# DRV10987.net
KiCad netlist of a schematic drawn in EAGLE
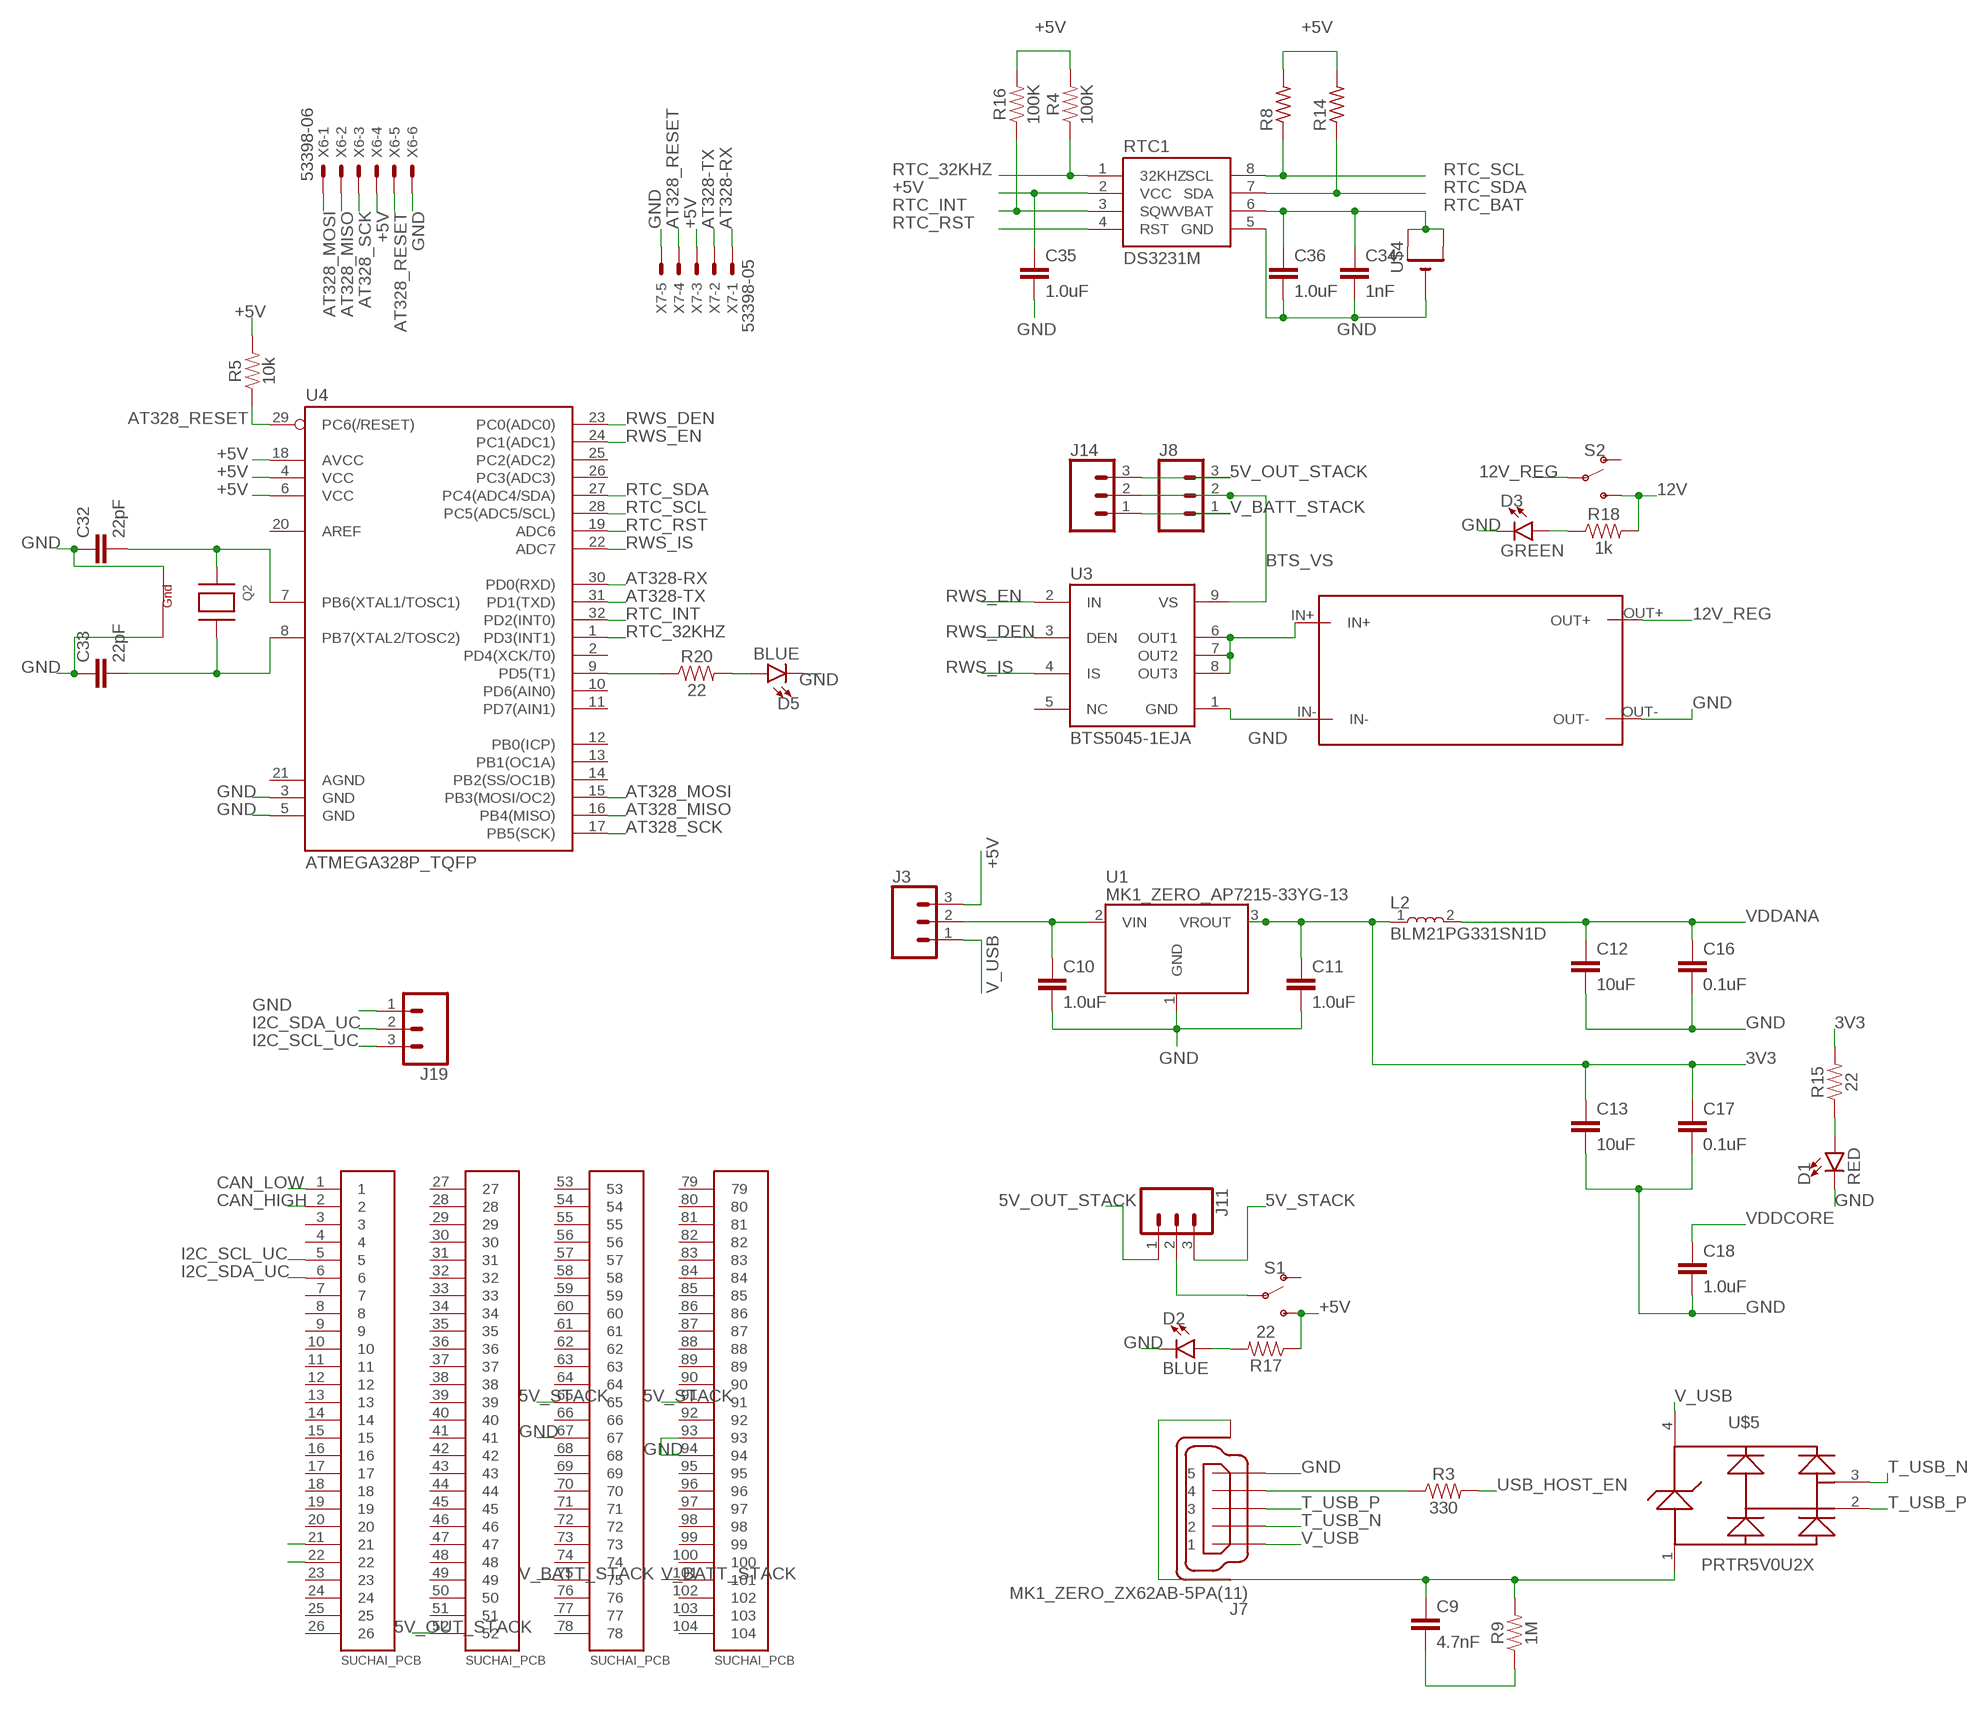
[diagram p0: schematic, sheet 1, part 1 of 2]
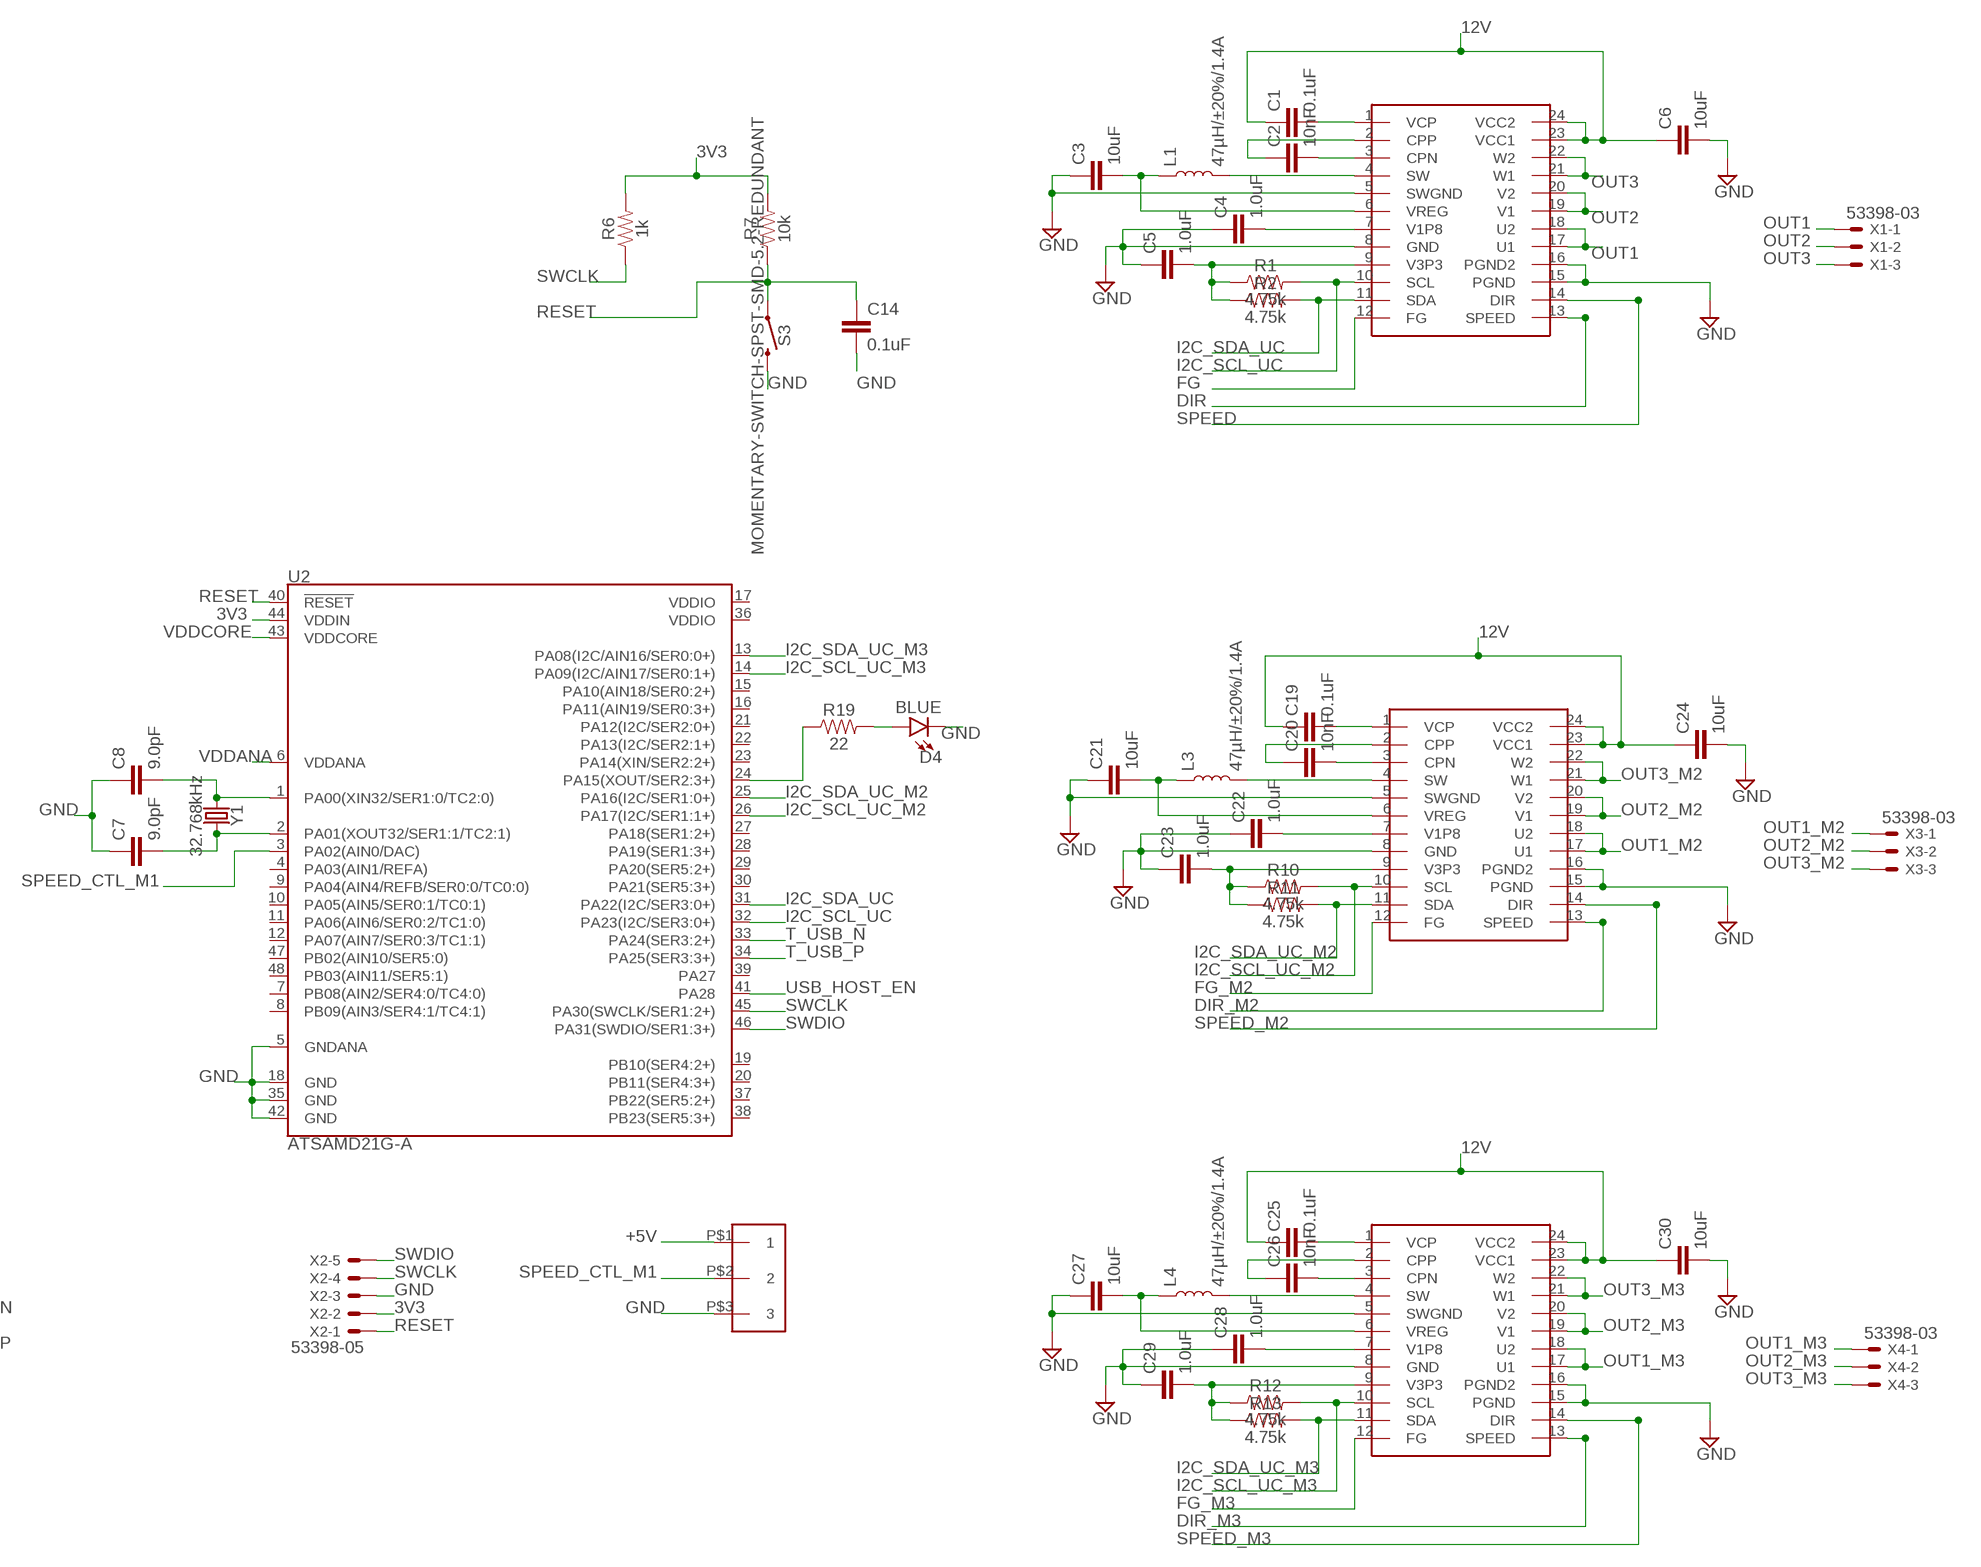
[diagram p1: schematic, sheet 1, part 2 of 2]

(export (version "E")
  (design (tool "Eeschema 10.0.6"))
  (components
    (comp (ref "C1")
      (value "0.1uF")
      (footprint "eagle-import:0805")
      (libsource (lib "eagle-import") (part "1.0UF-0805-25V-10%"))
    )
    (comp (ref "C2")
      (value "10nF")
      (footprint "eagle-import:0805")
      (libsource (lib "eagle-import") (part "1.0UF-0805-25V-10%"))
    )
    (comp (ref "C3")
      (value "10uF")
      (footprint "eagle-import:0805")
      (libsource (lib "eagle-import") (part "1.0UF-0805-25V-10%"))
    )
    (comp (ref "C4")
      (value "1.0uF")
      (footprint "eagle-import:0805")
      (libsource (lib "eagle-import") (part "1.0UF-0805-25V-10%"))
    )
    (comp (ref "C5")
      (value "1.0uF")
      (footprint "eagle-import:0805")
      (libsource (lib "eagle-import") (part "1.0UF-0805-25V-10%"))
    )
    (comp (ref "C6")
      (value "10uF")
      (footprint "eagle-import:0805")
      (libsource (lib "eagle-import") (part "1.0UF-0805-25V-10%"))
    )
    (comp (ref "C7")
      (value "9.0pF")
      (footprint "eagle-import:0603")
      (libsource (lib "eagle-import") (part "9.0PF-0603-50V-10%"))
    )
    (comp (ref "C8")
      (value "9.0pF")
      (footprint "eagle-import:0603")
      (libsource (lib "eagle-import") (part "9.0PF-0603-50V-10%"))
    )
    (comp (ref "C9")
      (value "4.7nF")
      (footprint "eagle-import:0603")
      (libsource (lib "eagle-import") (part "4.7PF-0603-50V-5%"))
    )
    (comp (ref "C10")
      (value "1.0uF")
      (footprint "eagle-import:0805")
      (libsource (lib "eagle-import") (part "1.0UF-0805-25V-(+80/-20%)"))
    )
    (comp (ref "C11")
      (value "1.0uF")
      (footprint "eagle-import:0805")
      (libsource (lib "eagle-import") (part "1.0UF-0805-25V-(+80/-20%)"))
    )
    (comp (ref "C12")
      (value "10uF")
      (footprint "eagle-import:0805")
      (libsource (lib "eagle-import") (part "10UF-0805-10V-10%"))
    )
    (comp (ref "C13")
      (value "10uF")
      (footprint "eagle-import:0805")
      (libsource (lib "eagle-import") (part "10UF-0805-10V-10%"))
    )
    (comp (ref "C14")
      (value "0.1uF")
      (footprint "eagle-import:0805")
      (libsource (lib "eagle-import") (part "1.0UF-0805-25V-(+80/-20%)"))
    )
    (comp (ref "C16")
      (value "0.1uF")
      (footprint "eagle-import:0805")
      (libsource (lib "eagle-import") (part "1.0UF-0805-25V-(+80/-20%)"))
    )
    (comp (ref "C17")
      (value "0.1uF")
      (footprint "eagle-import:0805")
      (libsource (lib "eagle-import") (part "1.0UF-0805-25V-(+80/-20%)"))
    )
    (comp (ref "C18")
      (value "1.0uF")
      (footprint "eagle-import:0805")
      (libsource (lib "eagle-import") (part "1.0UF-0805-25V-(+80/-20%)"))
    )
    (comp (ref "C19")
      (value "0.1uF")
      (footprint "eagle-import:0805")
      (libsource (lib "eagle-import") (part "1.0UF-0805-25V-10%"))
    )
    (comp (ref "C20")
      (value "10nF")
      (footprint "eagle-import:0805")
      (libsource (lib "eagle-import") (part "1.0UF-0805-25V-10%"))
    )
    (comp (ref "C21")
      (value "10uF")
      (footprint "eagle-import:0805")
      (libsource (lib "eagle-import") (part "1.0UF-0805-25V-10%"))
    )
    (comp (ref "C22")
      (value "1.0uF")
      (footprint "eagle-import:0805")
      (libsource (lib "eagle-import") (part "1.0UF-0805-25V-10%"))
    )
    (comp (ref "C23")
      (value "1.0uF")
      (footprint "eagle-import:0805")
      (libsource (lib "eagle-import") (part "1.0UF-0805-25V-10%"))
    )
    (comp (ref "C24")
      (value "10uF")
      (footprint "eagle-import:0805")
      (libsource (lib "eagle-import") (part "1.0UF-0805-25V-10%"))
    )
    (comp (ref "C25")
      (value "0.1uF")
      (footprint "eagle-import:0805")
      (libsource (lib "eagle-import") (part "1.0UF-0805-25V-10%"))
    )
    (comp (ref "C26")
      (value "10nF")
      (footprint "eagle-import:0805")
      (libsource (lib "eagle-import") (part "1.0UF-0805-25V-10%"))
    )
    (comp (ref "C27")
      (value "10uF")
      (footprint "eagle-import:0805")
      (libsource (lib "eagle-import") (part "1.0UF-0805-25V-10%"))
    )
    (comp (ref "C28")
      (value "1.0uF")
      (footprint "eagle-import:0805")
      (libsource (lib "eagle-import") (part "1.0UF-0805-25V-10%"))
    )
    (comp (ref "C29")
      (value "1.0uF")
      (footprint "eagle-import:0805")
      (libsource (lib "eagle-import") (part "1.0UF-0805-25V-10%"))
    )
    (comp (ref "C30")
      (value "10uF")
      (footprint "eagle-import:0805")
      (libsource (lib "eagle-import") (part "1.0UF-0805-25V-10%"))
    )
    (comp (ref "C32")
      (value "22pF")
      (footprint "eagle-import:0603")
      (libsource (lib "eagle-import") (part "22PF-0603-50V-5%"))
    )
    (comp (ref "C33")
      (value "22pF")
      (footprint "eagle-import:0603")
      (libsource (lib "eagle-import") (part "22PF-0603-50V-5%"))
    )
    (comp (ref "C34")
      (value "1nF")
      (footprint "eagle-import:0603")
      (libsource (lib "eagle-import") (part "1.0NF/1000PF-0603-50V-10%"))
    )
    (comp (ref "C35")
      (value "1.0uF")
      (footprint "eagle-import:0402")
      (libsource (lib "eagle-import") (part "1.0UF-0402-16V-10%"))
    )
    (comp (ref "C36")
      (value "1.0uF")
      (footprint "eagle-import:0402")
      (libsource (lib "eagle-import") (part "1.0UF-0402-16V-10%"))
    )
    (comp (ref "D1")
      (value "RED")
      (footprint "eagle-import:LED-0603")
      (libsource (lib "eagle-import") (part "LED-RED0603"))
    )
    (comp (ref "D2")
      (value "BLUE")
      (footprint "eagle-import:LED-0603")
      (libsource (lib "eagle-import") (part "LED-BLUE0603"))
    )
    (comp (ref "D3")
      (value "GREEN")
      (footprint "eagle-import:LED-0603")
      (libsource (lib "eagle-import") (part "LED-GREEN0603"))
    )
    (comp (ref "D4")
      (value "BLUE")
      (footprint "eagle-import:LED-0603")
      (libsource (lib "eagle-import") (part "LED-BLUE0603"))
    )
    (comp (ref "D5")
      (value "BLUE")
      (footprint "eagle-import:LED-0603")
      (libsource (lib "eagle-import") (part "LED-BLUE0603"))
    )
    (comp (ref "J1")
      (value "SUCHAI_PCB")
      (footprint "eagle-import:SUCHAI_PCB")
      (libsource (lib "eagle-import") (part "SUCHAI_PCB"))
    )
    (comp (ref "J3")
      (value "CONN_03LOCK_LONGPADS")
      (footprint "eagle-import:1X03_LOCK_LONGPADS")
      (libsource (lib "eagle-import") (part "CONN_03LOCK_LONGPADS"))
    )
    (comp (ref "J7")
      (value "MK1_ZERO_ZX62AB-5PA(11)")
      (footprint "eagle-import:MK1_ZERO_USBMICRO-ZX62-AB-5PA")
      (libsource (lib "eagle-import") (part "MK1_ZERO_ZX62AB-5PA(11)"))
    )
    (comp (ref "J8")
      (value "CONN_03LOCK")
      (footprint "eagle-import:1X03_LOCK")
      (libsource (lib "eagle-import") (part "CONN_03LOCK"))
    )
    (comp (ref "J11")
      (value "CONN_03LOCK")
      (footprint "eagle-import:1X03_LOCK")
      (libsource (lib "eagle-import") (part "CONN_03LOCK"))
    )
    (comp (ref "J14")
      (value "CONN_03LOCK")
      (footprint "eagle-import:1X03_LOCK")
      (libsource (lib "eagle-import") (part "CONN_03LOCK"))
    )
    (comp (ref "J19")
      (value "CONN_03LOCK")
      (footprint "eagle-import:1X03_LOCK")
      (libsource (lib "eagle-import") (part "CONN_03LOCK"))
    )
    (comp (ref "L1")
      (value "47µH/±20%/1.4A")
      (footprint "eagle-import:SRN6045")
      (libsource (lib "eagle-import") (part "INDUCTOR-SRN6045-33UH"))
    )
    (comp (ref "L2")
      (value "BLM21PG331SN1D")
      (footprint "eagle-import:INDC2012X87")
      (fields (field (name "MANUFACTURER") "MURATA"))
      (libsource (lib "eagle-import") (part "BLM21PG331SN1D"))
    )
    (comp (ref "L3")
      (value "47µH/±20%/1.4A")
      (footprint "eagle-import:SRN6045")
      (libsource (lib "eagle-import") (part "INDUCTOR-SRN6045-33UH"))
    )
    (comp (ref "L4")
      (value "47µH/±20%/1.4A")
      (footprint "eagle-import:SRN6045")
      (libsource (lib "eagle-import") (part "INDUCTOR-SRN6045-33UH"))
    )
    (comp (ref "Q2")
      (value "XTAL-4-3225")
      (footprint "eagle-import:NX3225")
      (libsource (lib "eagle-import") (part "XTAL-4-3225"))
    )
    (comp (ref "R1")
      (value "4.75k")
      (footprint "eagle-import:0805")
      (libsource (lib "eagle-import") (part "RESISTOR0805"))
    )
    (comp (ref "R2")
      (value "4.75k")
      (footprint "eagle-import:0805")
      (libsource (lib "eagle-import") (part "RESISTOR0805"))
    )
    (comp (ref "R3")
      (value "330")
      (footprint "eagle-import:0603")
      (libsource (lib "eagle-import") (part "330OHM-0603-1/10W-1%"))
    )
    (comp (ref "R4")
      (value "100K")
      (footprint "eagle-import:0402")
      (libsource (lib "eagle-import") (part "100KOHM-0402-1/16W-1%"))
    )
    (comp (ref "R5")
      (value "10k")
      (footprint "eagle-import:0603")
      (libsource (lib "eagle-import") (part "10KOHM-0603-1/10W-1%"))
    )
    (comp (ref "R6")
      (value "1k")
      (footprint "eagle-import:0603")
      (libsource (lib "eagle-import") (part "1KOHM-0603-1/10W-1%"))
    )
    (comp (ref "R7")
      (value "10k")
      (footprint "eagle-import:0603")
      (libsource (lib "eagle-import") (part "10KOHM-0603-1/10W-1%"))
    )
    (comp (ref "R8")
      (value "R-US_R0402")
      (footprint "eagle-import:R0402")
      (libsource (lib "eagle-import") (part "R-US_R0402"))
    )
    (comp (ref "R9")
      (value "1M")
      (footprint "eagle-import:0603")
      (libsource (lib "eagle-import") (part "1MOHM-0603-1/4W-5%"))
    )
    (comp (ref "R10")
      (value "4.75k")
      (footprint "eagle-import:0805")
      (libsource (lib "eagle-import") (part "RESISTOR0805"))
    )
    (comp (ref "R11")
      (value "4.75k")
      (footprint "eagle-import:0805")
      (libsource (lib "eagle-import") (part "RESISTOR0805"))
    )
    (comp (ref "R12")
      (value "4.75k")
      (footprint "eagle-import:0805")
      (libsource (lib "eagle-import") (part "RESISTOR0805"))
    )
    (comp (ref "R13")
      (value "4.75k")
      (footprint "eagle-import:0805")
      (libsource (lib "eagle-import") (part "RESISTOR0805"))
    )
    (comp (ref "R14")
      (value "R-US_R0402")
      (footprint "eagle-import:R0402")
      (libsource (lib "eagle-import") (part "R-US_R0402"))
    )
    (comp (ref "R15")
      (value "22")
      (footprint "eagle-import:0603")
      (libsource (lib "eagle-import") (part "22OHM-0603-1/10W-1%"))
    )
    (comp (ref "R16")
      (value "100K")
      (footprint "eagle-import:0402")
      (libsource (lib "eagle-import") (part "100KOHM-0402-1/16W-1%"))
    )
    (comp (ref "R17")
      (value "22")
      (footprint "eagle-import:0603")
      (libsource (lib "eagle-import") (part "22OHM-0603-1/10W-1%"))
    )
    (comp (ref "R18")
      (value "1k")
      (footprint "eagle-import:0603")
      (libsource (lib "eagle-import") (part "1KOHM-0603-1/10W-1%"))
    )
    (comp (ref "R19")
      (value "22")
      (footprint "eagle-import:0603")
      (libsource (lib "eagle-import") (part "22OHM-0603-1/10W-1%"))
    )
    (comp (ref "R20")
      (value "22")
      (footprint "eagle-import:0603")
      (libsource (lib "eagle-import") (part "22OHM-0603-1/10W-1%"))
    )
    (comp (ref "RTC1")
      (value "DS3231M")
      (footprint "eagle-import:SO08")
      (libsource (lib "eagle-import") (part "DS3231M"))
    )
    (comp (ref "S1")
      (value "SWITCH-SPDT-PTH-11.6X4.0MM")
      (footprint "eagle-import:SWITCH_SPDT_PTH_11.6X4.0MM")
      (libsource (lib "eagle-import") (part "SWITCH-SPDT-PTH-11.6X4.0MM"))
    )
    (comp (ref "S2")
      (value "SWITCH-SPDT-PTH-11.6X4.0MM")
      (footprint "eagle-import:SWITCH_SPDT_PTH_11.6X4.0MM")
      (libsource (lib "eagle-import") (part "SWITCH-SPDT-PTH-11.6X4.0MM"))
    )
    (comp (ref "S3")
      (value "MOMENTARY-SWITCH-SPST-SMD-5.2-REDUNDANT")
      (footprint "eagle-import:TACTILE_SWITCH_SMD_5.2MM")
      (libsource (lib "eagle-import") (part "MOMENTARY-SWITCH-SPST-SMD-5.2-REDUNDANT"))
    )
    (comp (ref "U$1")
      (value "DRV10987")
      (footprint "eagle-import:DRV10987")
      (libsource (lib "eagle-import") (part "DRV10987"))
    )
    (comp (ref "U$2")
      (value "XL6009E1_MODULE")
      (footprint "eagle-import:XL6009E1_MODULE")
      (libsource (lib "eagle-import") (part "XL6009E1_MODULE"))
    )
    (comp (ref "U$3")
      (value "CONN_03_SMD_SMALL")
      (footprint "eagle-import:CONN_03_SMD_SMALL")
      (libsource (lib "eagle-import") (part "CONN_03_SMD_SMALL"))
    )
    (comp (ref "U$4")
      (value "CR1220SMT")
      (footprint "eagle-import:CR1220-SMD")
      (libsource (lib "eagle-import") (part "CR1220SMT"))
    )
    (comp (ref "U$5")
      (value "ARDUINO_PRTR5V0U2XB")
      (footprint "eagle-import:ARDUINO_SOT143B")
      (libsource (lib "eagle-import") (part "ARDUINO_PRTR5V0U2XB"))
    )
    (comp (ref "U$6")
      (value "DRV10987")
      (footprint "eagle-import:DRV10987")
      (libsource (lib "eagle-import") (part "DRV10987"))
    )
    (comp (ref "U$7")
      (value "DRV10987")
      (footprint "eagle-import:DRV10987")
      (libsource (lib "eagle-import") (part "DRV10987"))
    )
    (comp (ref "U1")
      (value "MK1_ZERO_AP7215-33YG-13")
      (footprint "eagle-import:MK1_ZERO_SOT150P400X160-3N")
      (fields (field (name "MF") "Diodes Inc ") (field (name "MPN") "AP7215-33YG-13 "))
      (libsource (lib "eagle-import") (part "MK1_ZERO_AP7215-33YG-13"))
    )
    (comp (ref "U2")
      (value "ATSAMD21G-A")
      (footprint "eagle-import:TQFP-48")
      (libsource (lib "eagle-import") (part "ATSAMD21G-A"))
    )
    (comp (ref "U3")
      (value "BTS5045-1EJA")
      (footprint "eagle-import:SOIC127P600X170-9N")
      (libsource (lib "eagle-import") (part "BTS5045-1EJA"))
    )
    (comp (ref "U4")
      (value "ATMEGA328P_TQFP")
      (footprint "eagle-import:TQFP32-08")
      (libsource (lib "eagle-import") (part "ATMEGA328P_TQFP"))
    )
    (comp (ref "X1")
      (value "53398-03")
      (footprint "eagle-import:53398-03")
      (fields (field (name "MF") "MOLEX"))
      (libsource (lib "eagle-import") (part "53?-03398"))
    )
    (comp (ref "X2")
      (value "53398-05")
      (footprint "eagle-import:53398-05")
      (fields (field (name "MF") "MOLEX"))
      (libsource (lib "eagle-import") (part "53?-05398"))
    )
    (comp (ref "X3")
      (value "53398-03")
      (footprint "eagle-import:53398-03")
      (fields (field (name "MF") "MOLEX"))
      (libsource (lib "eagle-import") (part "53?-03398"))
    )
    (comp (ref "X4")
      (value "53398-03")
      (footprint "eagle-import:53398-03")
      (fields (field (name "MF") "MOLEX"))
      (libsource (lib "eagle-import") (part "53?-03398"))
    )
    (comp (ref "X6")
      (value "53398-06")
      (footprint "eagle-import:53398-06")
      (fields (field (name "MF") "MOLEX"))
      (libsource (lib "eagle-import") (part "53?-06398"))
    )
    (comp (ref "X7")
      (value "53398-05")
      (footprint "eagle-import:53398-05")
      (fields (field (name "MF") "MOLEX"))
      (libsource (lib "eagle-import") (part "53?-05398"))
    )
    (comp (ref "Y1")
      (value "32.768kHz")
      (footprint "eagle-import:CRYSTAL-SMD-3.2X1.5MM")
      (libsource (lib "eagle-import") (part "CRYSTAL-32.768KHZSMD-3.2X1.5"))
    )
  )
  (nets
    (net (code "1") (name "/+5V") (class "Default")
      (node (ref "C35") (pin "1") (pinfunction "1_1") (pintype "passive"))
      (node (ref "J3") (pin "3") (pinfunction "3_3") (pintype "passive"))
      (node (ref "R14") (pin "2") (pinfunction "2_2") (pintype "passive"))
      (node (ref "R16") (pin "2") (pinfunction "2_2") (pintype "passive"))
      (node (ref "R17") (pin "1") (pinfunction "1_1") (pintype "passive"))
      (node (ref "R4") (pin "2") (pinfunction "2_2") (pintype "passive"))
      (node (ref "R5") (pin "2") (pinfunction "2_2") (pintype "passive"))
      (node (ref "R8") (pin "2") (pinfunction "2_2") (pintype "passive"))
      (node (ref "RTC1") (pin "2") (pinfunction "VCC_2") (pintype "power_in"))
      (node (ref "S1") (pin "3") (pinfunction "S_3") (pintype "passive"))
      (node (ref "U$3") (pin "P$1") (pinfunction "1_P$1") (pintype "bidirectional"))
      (node (ref "U4") (pin "18") (pinfunction "AVCC_18") (pintype "bidirectional"))
      (node (ref "U4") (pin "4") (pinfunction "VCC_4") (pintype "bidirectional"))
      (node (ref "U4") (pin "6") (pinfunction "VCC_6") (pintype "bidirectional"))
      (node (ref "X6") (pin "4") (pinfunction "S_4") (pintype "passive"))
      (node (ref "X7") (pin "3") (pinfunction "S_3") (pintype "passive"))
    )
    (net (code "2") (name "/3V3") (class "Default")
      (node (ref "C11") (pin "1") (pinfunction "1_1") (pintype "passive"))
      (node (ref "C13") (pin "1") (pinfunction "1_1") (pintype "passive"))
      (node (ref "C17") (pin "1") (pinfunction "1_1") (pintype "passive"))
      (node (ref "L2") (pin "1") (pinfunction "1_1") (pintype "passive"))
      (node (ref "R15") (pin "2") (pinfunction "2_2") (pintype "passive"))
      (node (ref "R6") (pin "2") (pinfunction "2_2") (pintype "passive"))
      (node (ref "R7") (pin "2") (pinfunction "2_2") (pintype "passive"))
      (node (ref "U1") (pin "3") (pinfunction "VROUT_3") (pintype "power_in"))
      (node (ref "U2") (pin "44") (pinfunction "VDDIN_44") (pintype "bidirectional"))
      (node (ref "X2") (pin "2") (pinfunction "S_2") (pintype "passive"))
    )
    (net (code "3") (name "/5V_OUT_STACK") (class "Default")
      (node (ref "J1") (pin "52") (pinfunction "52_52") (pintype "bidirectional"))
      (node (ref "J11") (pin "1") (pinfunction "1_1") (pintype "passive"))
      (node (ref "J14") (pin "3") (pinfunction "3_3") (pintype "passive"))
      (node (ref "J8") (pin "3") (pinfunction "3_3") (pintype "passive"))
    )
    (net (code "4") (name "/5V_STACK") (class "Default")
      (node (ref "J1") (pin "65") (pinfunction "65_65") (pintype "bidirectional"))
      (node (ref "J1") (pin "91") (pinfunction "91_91") (pintype "bidirectional"))
      (node (ref "J11") (pin "3") (pinfunction "3_3") (pintype "passive"))
    )
    (net (code "5") (name "/12V") (class "Default")
      (node (ref "C1") (pin "1") (pinfunction "1_1") (pintype "passive"))
      (node (ref "C19") (pin "1") (pinfunction "1_1") (pintype "passive"))
      (node (ref "C24") (pin "1") (pinfunction "1_1") (pintype "passive"))
      (node (ref "C25") (pin "1") (pinfunction "1_1") (pintype "passive"))
      (node (ref "C30") (pin "1") (pinfunction "1_1") (pintype "passive"))
      (node (ref "C6") (pin "1") (pinfunction "1_1") (pintype "passive"))
      (node (ref "R18") (pin "2") (pinfunction "2_2") (pintype "passive"))
      (node (ref "S2") (pin "3") (pinfunction "S_3") (pintype "passive"))
      (node (ref "U$1") (pin "23") (pinfunction "VCC1_23") (pintype "bidirectional"))
      (node (ref "U$1") (pin "24") (pinfunction "VCC2_24") (pintype "bidirectional"))
      (node (ref "U$6") (pin "23") (pinfunction "VCC1_23") (pintype "bidirectional"))
      (node (ref "U$6") (pin "24") (pinfunction "VCC2_24") (pintype "bidirectional"))
      (node (ref "U$7") (pin "23") (pinfunction "VCC1_23") (pintype "bidirectional"))
      (node (ref "U$7") (pin "24") (pinfunction "VCC2_24") (pintype "bidirectional"))
    )
    (net (code "6") (name "/12V_REG") (class "Default")
      (node (ref "S2") (pin "2") (pinfunction "P_2") (pintype "passive"))
      (node (ref "U$2") (pin "OUT+") (pinfunction "OUT+_OUT+") (pintype "bidirectional"))
    )
    (net (code "7") (name "/AT328-RX") (class "Default")
      (node (ref "U4") (pin "30") (pinfunction "PD0(RXD)_30") (pintype "bidirectional"))
      (node (ref "X7") (pin "1") (pinfunction "S_1") (pintype "passive"))
    )
    (net (code "8") (name "/AT328-TX") (class "Default")
      (node (ref "U4") (pin "31") (pinfunction "PD1(TXD)_31") (pintype "bidirectional"))
      (node (ref "X7") (pin "2") (pinfunction "S_2") (pintype "passive"))
    )
    (net (code "9") (name "/AT328_MISO") (class "Default")
      (node (ref "U4") (pin "16") (pinfunction "PB4(MISO)_16") (pintype "bidirectional"))
      (node (ref "X6") (pin "2") (pinfunction "S_2") (pintype "passive"))
    )
    (net (code "10") (name "/AT328_MOSI") (class "Default")
      (node (ref "U4") (pin "15") (pinfunction "PB3(MOSI/OC2)_15") (pintype "bidirectional"))
      (node (ref "X6") (pin "1") (pinfunction "S_1") (pintype "passive"))
    )
    (net (code "11") (name "/AT328_RESET") (class "Default")
      (node (ref "R5") (pin "1") (pinfunction "1_1") (pintype "passive"))
      (node (ref "U4") (pin "29") (pinfunction "PC6(/RESET)_29") (pintype "bidirectional"))
      (node (ref "X6") (pin "5") (pinfunction "S_5") (pintype "passive"))
      (node (ref "X7") (pin "4") (pinfunction "S_4") (pintype "passive"))
    )
    (net (code "12") (name "/AT328_SCK") (class "Default")
      (node (ref "U4") (pin "17") (pinfunction "PB5(SCK)_17") (pintype "bidirectional"))
      (node (ref "X6") (pin "3") (pinfunction "S_3") (pintype "passive"))
    )
    (net (code "13") (name "/BTS_VS") (class "Default")
      (node (ref "J14") (pin "2") (pinfunction "2_2") (pintype "passive"))
      (node (ref "J8") (pin "2") (pinfunction "2_2") (pintype "passive"))
      (node (ref "U3") (pin "9") (pinfunction "VS_9") (pintype "power_in"))
    )
    (net (code "14") (name "/CAN_HIGH") (class "Default")
      (node (ref "J1") (pin "2") (pinfunction "2_2") (pintype "bidirectional"))
    )
    (net (code "15") (name "/CAN_LOW") (class "Default")
      (node (ref "J1") (pin "1") (pinfunction "1_1") (pintype "bidirectional"))
    )
    (net (code "16") (name "/DIR") (class "Default")
      (node (ref "U$1") (pin "13") (pinfunction "SPEED_13") (pintype "bidirectional"))
    )
    (net (code "17") (name "/DIR_M2") (class "Default")
      (node (ref "U$6") (pin "13") (pinfunction "SPEED_13") (pintype "bidirectional"))
    )
    (net (code "18") (name "/DIR_M3") (class "Default")
      (node (ref "U$7") (pin "13") (pinfunction "SPEED_13") (pintype "bidirectional"))
    )
    (net (code "19") (name "/FG") (class "Default")
      (node (ref "U$1") (pin "12") (pinfunction "FG_12") (pintype "bidirectional"))
    )
    (net (code "20") (name "/FG_M2") (class "Default")
      (node (ref "U$6") (pin "12") (pinfunction "FG_12") (pintype "bidirectional"))
    )
    (net (code "21") (name "/FG_M3") (class "Default")
      (node (ref "U$7") (pin "12") (pinfunction "FG_12") (pintype "bidirectional"))
    )
    (net (code "22") (name "/I2C_SCL_UC") (class "Default")
      (node (ref "J1") (pin "5") (pinfunction "5_5") (pintype "bidirectional"))
      (node (ref "J19") (pin "3") (pinfunction "3_3") (pintype "passive"))
      (node (ref "R1") (pin "2") (pinfunction "2_2") (pintype "passive"))
      (node (ref "U$1") (pin "10") (pinfunction "SCL_10") (pintype "bidirectional"))
      (node (ref "U2") (pin "32") (pinfunction "PA23(I2C/SER3:0+)_32") (pintype "bidirectional"))
    )
    (net (code "23") (name "/I2C_SCL_UC_M2") (class "Default")
      (node (ref "R10") (pin "2") (pinfunction "2_2") (pintype "passive"))
      (node (ref "U$6") (pin "10") (pinfunction "SCL_10") (pintype "bidirectional"))
      (node (ref "U2") (pin "26") (pinfunction "PA17(I2C/SER1:1+)_26") (pintype "bidirectional"))
    )
    (net (code "24") (name "/I2C_SCL_UC_M3") (class "Default")
      (node (ref "R12") (pin "2") (pinfunction "2_2") (pintype "passive"))
      (node (ref "U$7") (pin "10") (pinfunction "SCL_10") (pintype "bidirectional"))
      (node (ref "U2") (pin "14") (pinfunction "PA09(I2C/AIN17/SER0:1+)_14") (pintype "bidirectional"))
    )
    (net (code "25") (name "/I2C_SDA_UC") (class "Default")
      (node (ref "J1") (pin "6") (pinfunction "6_6") (pintype "bidirectional"))
      (node (ref "J19") (pin "2") (pinfunction "2_2") (pintype "passive"))
      (node (ref "R2") (pin "2") (pinfunction "2_2") (pintype "passive"))
      (node (ref "U$1") (pin "11") (pinfunction "SDA_11") (pintype "bidirectional"))
      (node (ref "U2") (pin "31") (pinfunction "PA22(I2C/SER3:0+)_31") (pintype "bidirectional"))
    )
    (net (code "26") (name "/I2C_SDA_UC_M2") (class "Default")
      (node (ref "R11") (pin "2") (pinfunction "2_2") (pintype "passive"))
      (node (ref "U$6") (pin "11") (pinfunction "SDA_11") (pintype "bidirectional"))
      (node (ref "U2") (pin "25") (pinfunction "PA16(I2C/SER1:0+)_25") (pintype "bidirectional"))
    )
    (net (code "27") (name "/I2C_SDA_UC_M3") (class "Default")
      (node (ref "R13") (pin "2") (pinfunction "2_2") (pintype "passive"))
      (node (ref "U$7") (pin "11") (pinfunction "SDA_11") (pintype "bidirectional"))
      (node (ref "U2") (pin "13") (pinfunction "PA08(I2C/AIN16/SER0:0+)_13") (pintype "bidirectional"))
    )
    (net (code "28") (name "/OUT1") (class "Default")
      (node (ref "U$1") (pin "17") (pinfunction "U1_17") (pintype "bidirectional"))
      (node (ref "U$1") (pin "18") (pinfunction "U2_18") (pintype "bidirectional"))
      (node (ref "X1") (pin "1") (pinfunction "S_1") (pintype "passive"))
    )
    (net (code "29") (name "/OUT1_M2") (class "Default")
      (node (ref "U$6") (pin "17") (pinfunction "U1_17") (pintype "bidirectional"))
      (node (ref "U$6") (pin "18") (pinfunction "U2_18") (pintype "bidirectional"))
      (node (ref "X3") (pin "1") (pinfunction "S_1") (pintype "passive"))
    )
    (net (code "30") (name "/OUT1_M3") (class "Default")
      (node (ref "U$7") (pin "17") (pinfunction "U1_17") (pintype "bidirectional"))
      (node (ref "U$7") (pin "18") (pinfunction "U2_18") (pintype "bidirectional"))
      (node (ref "X4") (pin "1") (pinfunction "S_1") (pintype "passive"))
    )
    (net (code "31") (name "/OUT2") (class "Default")
      (node (ref "U$1") (pin "19") (pinfunction "V1_19") (pintype "bidirectional"))
      (node (ref "U$1") (pin "20") (pinfunction "V2_20") (pintype "bidirectional"))
      (node (ref "X1") (pin "2") (pinfunction "S_2") (pintype "passive"))
    )
    (net (code "32") (name "/OUT2_M2") (class "Default")
      (node (ref "U$6") (pin "19") (pinfunction "V1_19") (pintype "bidirectional"))
      (node (ref "U$6") (pin "20") (pinfunction "V2_20") (pintype "bidirectional"))
      (node (ref "X3") (pin "2") (pinfunction "S_2") (pintype "passive"))
    )
    (net (code "33") (name "/OUT2_M3") (class "Default")
      (node (ref "U$7") (pin "19") (pinfunction "V1_19") (pintype "bidirectional"))
      (node (ref "U$7") (pin "20") (pinfunction "V2_20") (pintype "bidirectional"))
      (node (ref "X4") (pin "2") (pinfunction "S_2") (pintype "passive"))
    )
    (net (code "34") (name "/OUT3") (class "Default")
      (node (ref "U$1") (pin "21") (pinfunction "W1_21") (pintype "bidirectional"))
      (node (ref "U$1") (pin "22") (pinfunction "W2_22") (pintype "bidirectional"))
      (node (ref "X1") (pin "3") (pinfunction "S_3") (pintype "passive"))
    )
    (net (code "35") (name "/OUT3_M2") (class "Default")
      (node (ref "U$6") (pin "21") (pinfunction "W1_21") (pintype "bidirectional"))
      (node (ref "U$6") (pin "22") (pinfunction "W2_22") (pintype "bidirectional"))
      (node (ref "X3") (pin "3") (pinfunction "S_3") (pintype "passive"))
    )
    (net (code "36") (name "/OUT3_M3") (class "Default")
      (node (ref "U$7") (pin "21") (pinfunction "W1_21") (pintype "bidirectional"))
      (node (ref "U$7") (pin "22") (pinfunction "W2_22") (pintype "bidirectional"))
      (node (ref "X4") (pin "3") (pinfunction "S_3") (pintype "passive"))
    )
    (net (code "37") (name "/RESET") (class "Default")
      (node (ref "C14") (pin "1") (pinfunction "1_1") (pintype "passive"))
      (node (ref "R7") (pin "1") (pinfunction "1_1") (pintype "passive"))
      (node (ref "S3") (pin "1") (pinfunction "1_1") (pintype "passive"))
      (node (ref "S3") (pin "2") (pinfunction "1_2") (pintype "passive"))
      (node (ref "U2") (pin "40") (pinfunction "~{RESET}_40") (pintype "bidirectional"))
      (node (ref "X2") (pin "1") (pinfunction "S_1") (pintype "passive"))
    )
    (net (code "38") (name "/RTC_32KHZ") (class "Default")
      (node (ref "R4") (pin "1") (pinfunction "1_1") (pintype "passive"))
      (node (ref "RTC1") (pin "1") (pinfunction "32KHZ_1") (pintype "output"))
      (node (ref "U4") (pin "1") (pinfunction "PD3(INT1)_1") (pintype "bidirectional"))
    )
    (net (code "39") (name "/RTC_BAT") (class "Default")
      (node (ref "C34") (pin "1") (pinfunction "1_1") (pintype "passive"))
      (node (ref "C36") (pin "1") (pinfunction "1_1") (pintype "passive"))
      (node (ref "RTC1") (pin "6") (pinfunction "VBAT_6") (pintype "power_in"))
      (node (ref "U$4") (pin "+$1") (pinfunction "+_+$1") (pintype "passive"))
      (node (ref "U$4") (pin "+$2") (pinfunction "+1_+$2") (pintype "passive"))
    )
    (net (code "40") (name "/RTC_INT") (class "Default")
      (node (ref "R16") (pin "1") (pinfunction "1_1") (pintype "passive"))
      (node (ref "RTC1") (pin "3") (pinfunction "SQW_3") (pintype "output"))
      (node (ref "U4") (pin "32") (pinfunction "PD2(INT0)_32") (pintype "bidirectional"))
    )
    (net (code "41") (name "/RTC_RST") (class "Default")
      (node (ref "RTC1") (pin "4") (pinfunction "RST_4") (pintype "bidirectional"))
      (node (ref "U4") (pin "19") (pinfunction "ADC6_19") (pintype "bidirectional"))
    )
    (net (code "42") (name "/RTC_SCL") (class "Default")
      (node (ref "R8") (pin "1") (pinfunction "1_1") (pintype "passive"))
      (node (ref "RTC1") (pin "8") (pinfunction "SCL_8") (pintype "bidirectional"))
      (node (ref "U4") (pin "28") (pinfunction "PC5(ADC5/SCL)_28") (pintype "bidirectional"))
    )
    (net (code "43") (name "/RTC_SDA") (class "Default")
      (node (ref "R14") (pin "1") (pinfunction "1_1") (pintype "passive"))
      (node (ref "RTC1") (pin "7") (pinfunction "SDA_7") (pintype "bidirectional"))
      (node (ref "U4") (pin "27") (pinfunction "PC4(ADC4/SDA)_27") (pintype "bidirectional"))
    )
    (net (code "44") (name "/RWS_DEN") (class "Default")
      (node (ref "U3") (pin "3") (pinfunction "DEN_3") (pintype "input"))
      (node (ref "U4") (pin "23") (pinfunction "PC0(ADC0)_23") (pintype "bidirectional"))
    )
    (net (code "45") (name "/RWS_EN") (class "Default")
      (node (ref "U3") (pin "2") (pinfunction "IN_2") (pintype "input"))
      (node (ref "U4") (pin "24") (pinfunction "PC1(ADC1)_24") (pintype "bidirectional"))
    )
    (net (code "46") (name "/RWS_IS") (class "Default")
      (node (ref "U3") (pin "4") (pinfunction "IS_4") (pintype "output"))
      (node (ref "U4") (pin "22") (pinfunction "ADC7_22") (pintype "bidirectional"))
    )
    (net (code "47") (name "/SPEED") (class "Default")
      (node (ref "U$1") (pin "14") (pinfunction "DIR_14") (pintype "bidirectional"))
    )
    (net (code "48") (name "/SPEED_CTL_M1") (class "Default")
      (node (ref "U$3") (pin "P$2") (pinfunction "2_P$2") (pintype "bidirectional"))
      (node (ref "U2") (pin "3") (pinfunction "PA02(AIN0/DAC)_3") (pintype "bidirectional"))
    )
    (net (code "49") (name "/SPEED_M2") (class "Default")
      (node (ref "U$6") (pin "14") (pinfunction "DIR_14") (pintype "bidirectional"))
    )
    (net (code "50") (name "/SPEED_M3") (class "Default")
      (node (ref "U$7") (pin "14") (pinfunction "DIR_14") (pintype "bidirectional"))
    )
    (net (code "51") (name "/SWCLK") (class "Default")
      (node (ref "R6") (pin "1") (pinfunction "1_1") (pintype "passive"))
      (node (ref "U2") (pin "45") (pinfunction "PA30(SWCLK/SER1:2+)_45") (pintype "bidirectional"))
      (node (ref "X2") (pin "4") (pinfunction "S_4") (pintype "passive"))
    )
    (net (code "52") (name "/SWDIO") (class "Default")
      (node (ref "U2") (pin "46") (pinfunction "PA31(SWDIO/SER1:3+)_46") (pintype "bidirectional"))
      (node (ref "X2") (pin "5") (pinfunction "S_5") (pintype "passive"))
    )
    (net (code "53") (name "/T_USB_N") (class "Default")
      (node (ref "J7") (pin "2") (pinfunction "2_2") (pintype "passive"))
      (node (ref "U$5") (pin "3") (pinfunction "3_3") (pintype "bidirectional"))
      (node (ref "U2") (pin "33") (pinfunction "PA24(SER3:2+)_33") (pintype "bidirectional"))
    )
    (net (code "54") (name "/T_USB_P") (class "Default")
      (node (ref "J7") (pin "3") (pinfunction "3_3") (pintype "passive"))
      (node (ref "U$5") (pin "2") (pinfunction "2_2") (pintype "bidirectional"))
      (node (ref "U2") (pin "34") (pinfunction "PA25(SER3:3+)_34") (pintype "bidirectional"))
    )
    (net (code "55") (name "/USB_HOST_EN") (class "Default")
      (node (ref "R3") (pin "2") (pinfunction "2_2") (pintype "passive"))
      (node (ref "U2") (pin "41") (pinfunction "PA28_41") (pintype "bidirectional"))
    )
    (net (code "56") (name "/VDDANA") (class "Default")
      (node (ref "C12") (pin "1") (pinfunction "1_1") (pintype "passive"))
      (node (ref "C16") (pin "1") (pinfunction "1_1") (pintype "passive"))
      (node (ref "L2") (pin "2") (pinfunction "2_2") (pintype "passive"))
      (node (ref "U2") (pin "6") (pinfunction "VDDANA_6") (pintype "bidirectional"))
    )
    (net (code "57") (name "/VDDCORE") (class "Default")
      (node (ref "C18") (pin "1") (pinfunction "1_1") (pintype "passive"))
      (node (ref "U2") (pin "43") (pinfunction "VDDCORE_43") (pintype "bidirectional"))
    )
    (net (code "58") (name "/V_BATT_STACK") (class "Default")
      (node (ref "J1") (pin "101") (pinfunction "101_101") (pintype "bidirectional"))
      (node (ref "J1") (pin "75") (pinfunction "75_75") (pintype "bidirectional"))
      (node (ref "J14") (pin "1") (pinfunction "1_1") (pintype "passive"))
      (node (ref "J8") (pin "1") (pinfunction "1_1") (pintype "passive"))
    )
    (net (code "59") (name "/V_USB") (class "Default")
      (node (ref "J3") (pin "1") (pinfunction "1_1") (pintype "passive"))
      (node (ref "J7") (pin "1") (pinfunction "1_1") (pintype "passive"))
      (node (ref "U$5") (pin "4") (pinfunction "4_4") (pintype "bidirectional"))
    )
    (net (code "60") (name "GND") (class "Default")
      (node (ref "C10") (pin "2") (pinfunction "2_2") (pintype "passive"))
      (node (ref "C11") (pin "2") (pinfunction "2_2") (pintype "passive"))
      (node (ref "C12") (pin "2") (pinfunction "2_2") (pintype "passive"))
      (node (ref "C13") (pin "2") (pinfunction "2_2") (pintype "passive"))
      (node (ref "C14") (pin "2") (pinfunction "2_2") (pintype "passive"))
      (node (ref "C16") (pin "2") (pinfunction "2_2") (pintype "passive"))
      (node (ref "C17") (pin "2") (pinfunction "2_2") (pintype "passive"))
      (node (ref "C18") (pin "2") (pinfunction "2_2") (pintype "passive"))
      (node (ref "C21") (pin "1") (pinfunction "1_1") (pintype "passive"))
      (node (ref "C22") (pin "1") (pinfunction "1_1") (pintype "passive"))
      (node (ref "C23") (pin "1") (pinfunction "1_1") (pintype "passive"))
      (node (ref "C24") (pin "2") (pinfunction "2_2") (pintype "passive"))
      (node (ref "C27") (pin "1") (pinfunction "1_1") (pintype "passive"))
      (node (ref "C28") (pin "1") (pinfunction "1_1") (pintype "passive"))
      (node (ref "C29") (pin "1") (pinfunction "1_1") (pintype "passive"))
      (node (ref "C3") (pin "1") (pinfunction "1_1") (pintype "passive"))
      (node (ref "C30") (pin "2") (pinfunction "2_2") (pintype "passive"))
      (node (ref "C32") (pin "1") (pinfunction "1_1") (pintype "passive"))
      (node (ref "C33") (pin "1") (pinfunction "1_1") (pintype "passive"))
      (node (ref "C34") (pin "2") (pinfunction "2_2") (pintype "passive"))
      (node (ref "C35") (pin "2") (pinfunction "2_2") (pintype "passive"))
      (node (ref "C36") (pin "2") (pinfunction "2_2") (pintype "passive"))
      (node (ref "C4") (pin "1") (pinfunction "1_1") (pintype "passive"))
      (node (ref "C5") (pin "1") (pinfunction "1_1") (pintype "passive"))
      (node (ref "C6") (pin "2") (pinfunction "2_2") (pintype "passive"))
      (node (ref "C7") (pin "1") (pinfunction "1_1") (pintype "passive"))
      (node (ref "C8") (pin "1") (pinfunction "1_1") (pintype "passive"))
      (node (ref "D1") (pin "C") (pinfunction "C_C") (pintype "passive"))
      (node (ref "D2") (pin "C") (pinfunction "C_C") (pintype "passive"))
      (node (ref "D3") (pin "C") (pinfunction "C_C") (pintype "passive"))
      (node (ref "D4") (pin "C") (pinfunction "C_C") (pintype "passive"))
      (node (ref "D5") (pin "C") (pinfunction "C_C") (pintype "passive"))
      (node (ref "J1") (pin "67") (pinfunction "67_67") (pintype "bidirectional"))
      (node (ref "J1") (pin "93") (pinfunction "93_93") (pintype "bidirectional"))
      (node (ref "J1") (pin "94") (pinfunction "94_94") (pintype "bidirectional"))
      (node (ref "J19") (pin "1") (pinfunction "1_1") (pintype "passive"))
      (node (ref "J7") (pin "5") (pinfunction "5_5") (pintype "passive"))
      (node (ref "Q2") (pin "2") (pinfunction "G2_2") (pintype "power_in"))
      (node (ref "Q2") (pin "4") (pinfunction "G1_4") (pintype "power_in"))
      (node (ref "RTC1") (pin "5") (pinfunction "GND_5") (pintype "power_in"))
      (node (ref "S3") (pin "3") (pinfunction "2_3") (pintype "passive"))
      (node (ref "S3") (pin "4") (pinfunction "2_4") (pintype "passive"))
      (node (ref "U$1") (pin "15") (pinfunction "PGND_15") (pintype "bidirectional"))
      (node (ref "U$1") (pin "16") (pinfunction "PGND2_16") (pintype "bidirectional"))
      (node (ref "U$1") (pin "5") (pinfunction "SWGND_5") (pintype "bidirectional"))
      (node (ref "U$1") (pin "8") (pinfunction "GND_8") (pintype "bidirectional"))
      (node (ref "U$2") (pin "IN-") (pinfunction "IN-_IN-") (pintype "bidirectional"))
      (node (ref "U$2") (pin "OUT-") (pinfunction "OUT-_OUT-") (pintype "bidirectional"))
      (node (ref "U$3") (pin "P$3") (pinfunction "3_P$3") (pintype "bidirectional"))
      (node (ref "U$4") (pin "-") (pinfunction "-_-") (pintype "passive"))
      (node (ref "U$6") (pin "15") (pinfunction "PGND_15") (pintype "bidirectional"))
      (node (ref "U$6") (pin "16") (pinfunction "PGND2_16") (pintype "bidirectional"))
      (node (ref "U$6") (pin "5") (pinfunction "SWGND_5") (pintype "bidirectional"))
      (node (ref "U$6") (pin "8") (pinfunction "GND_8") (pintype "bidirectional"))
      (node (ref "U$7") (pin "15") (pinfunction "PGND_15") (pintype "bidirectional"))
      (node (ref "U$7") (pin "16") (pinfunction "PGND2_16") (pintype "bidirectional"))
      (node (ref "U$7") (pin "5") (pinfunction "SWGND_5") (pintype "bidirectional"))
      (node (ref "U$7") (pin "8") (pinfunction "GND_8") (pintype "bidirectional"))
      (node (ref "U1") (pin "1") (pinfunction "GND_1") (pintype "power_in"))
      (node (ref "U2") (pin "18") (pinfunction "GND_18") (pintype "bidirectional"))
      (node (ref "U2") (pin "35") (pinfunction "GND_35") (pintype "bidirectional"))
      (node (ref "U2") (pin "42") (pinfunction "GND_42") (pintype "bidirectional"))
      (node (ref "U2") (pin "5") (pinfunction "GNDANA_5") (pintype "bidirectional"))
      (node (ref "U3") (pin "1") (pinfunction "GND_1") (pintype "power_in"))
      (node (ref "U4") (pin "3") (pinfunction "GND_3") (pintype "bidirectional"))
      (node (ref "U4") (pin "5") (pinfunction "GND_5") (pintype "bidirectional"))
      (node (ref "X2") (pin "3") (pinfunction "S_3") (pintype "passive"))
      (node (ref "X6") (pin "6") (pinfunction "S_6") (pintype "passive"))
      (node (ref "X7") (pin "5") (pinfunction "S_5") (pintype "passive"))
    )
    (net (code "61") (name "Net-(C9-Pad1)") (class "Default")
      (node (ref "C9") (pin "1") (pinfunction "1_1") (pintype "passive"))
      (node (ref "J7") (pin "10") (pinfunction "SH_10") (pintype "passive"))
      (node (ref "J7") (pin "11") (pinfunction "SH_11") (pintype "passive"))
      (node (ref "J7") (pin "6") (pinfunction "SH_6") (pintype "passive"))
      (node (ref "J7") (pin "7") (pinfunction "SH_7") (pintype "passive"))
      (node (ref "J7") (pin "8") (pinfunction "SH_8") (pintype "passive"))
      (node (ref "J7") (pin "9") (pinfunction "SH_9") (pintype "passive"))
      (node (ref "R9") (pin "2") (pinfunction "2_2") (pintype "passive"))
      (node (ref "U$5") (pin "1") (pinfunction "1_1") (pintype "bidirectional"))
    )
    (net (code "62") (name "Net-(C9-Pad2)") (class "Default")
      (node (ref "C9") (pin "2") (pinfunction "2_2") (pintype "passive"))
      (node (ref "R9") (pin "1") (pinfunction "1_1") (pintype "passive"))
    )
    (net (code "63") (name "Net-(D1-PadA)") (class "Default")
      (node (ref "D1") (pin "A") (pinfunction "A_A") (pintype "passive"))
      (node (ref "R15") (pin "1") (pinfunction "1_1") (pintype "passive"))
    )
    (net (code "64") (name "Net-(D2-PadA)") (class "Default")
      (node (ref "D2") (pin "A") (pinfunction "A_A") (pintype "passive"))
      (node (ref "R17") (pin "2") (pinfunction "2_2") (pintype "passive"))
    )
    (net (code "65") (name "Net-(D3-PadA)") (class "Default")
      (node (ref "D3") (pin "A") (pinfunction "A_A") (pintype "passive"))
      (node (ref "R18") (pin "1") (pinfunction "1_1") (pintype "passive"))
    )
    (net (code "66") (name "Net-(D4-PadA)") (class "Default")
      (node (ref "D4") (pin "A") (pinfunction "A_A") (pintype "passive"))
      (node (ref "R19") (pin "2") (pinfunction "2_2") (pintype "passive"))
    )
    (net (code "67") (name "Net-(D5-PadA)") (class "Default")
      (node (ref "D5") (pin "A") (pinfunction "A_A") (pintype "passive"))
      (node (ref "R20") (pin "2") (pinfunction "2_2") (pintype "passive"))
    )
    (net (code "68") (name "Net-(J7-Pad4)") (class "Default")
      (node (ref "J7") (pin "4") (pinfunction "4_4") (pintype "passive"))
      (node (ref "R3") (pin "1") (pinfunction "1_1") (pintype "passive"))
    )
    (net (code "69") (name "Net-(Q2-X1)") (class "Default")
      (node (ref "C32") (pin "2") (pinfunction "2_2") (pintype "passive"))
      (node (ref "Q2") (pin "1") (pinfunction "X1_1") (pintype "bidirectional"))
      (node (ref "U4") (pin "7") (pinfunction "PB6(XTAL1/TOSC1)_7") (pintype "bidirectional"))
    )
    (net (code "70") (name "Net-(Q2-X2)") (class "Default")
      (node (ref "C33") (pin "2") (pinfunction "2_2") (pintype "passive"))
      (node (ref "Q2") (pin "3") (pinfunction "X2_3") (pintype "bidirectional"))
      (node (ref "U4") (pin "8") (pinfunction "PB7(XTAL2/TOSC2)_8") (pintype "bidirectional"))
    )
    (net (code "71") (name "Net-(S1-P)") (class "Default")
      (node (ref "J11") (pin "2") (pinfunction "2_2") (pintype "passive"))
      (node (ref "S1") (pin "2") (pinfunction "P_2") (pintype "passive"))
    )
    (net (code "72") (name "Net-(U$1-CPN)") (class "Default")
      (node (ref "C2") (pin "2") (pinfunction "2_2") (pintype "passive"))
      (node (ref "U$1") (pin "3") (pinfunction "CPN_3") (pintype "bidirectional"))
    )
    (net (code "73") (name "Net-(U$1-CPP)") (class "Default")
      (node (ref "C2") (pin "1") (pinfunction "1_1") (pintype "passive"))
      (node (ref "U$1") (pin "2") (pinfunction "CPP_2") (pintype "bidirectional"))
    )
    (net (code "74") (name "Net-(U$1-SW)") (class "Default")
      (node (ref "L1") (pin "2") (pinfunction "2_2") (pintype "passive"))
      (node (ref "U$1") (pin "4") (pinfunction "SW_4") (pintype "bidirectional"))
    )
    (net (code "75") (name "Net-(U$1-V1P8)") (class "Default")
      (node (ref "C4") (pin "2") (pinfunction "2_2") (pintype "passive"))
      (node (ref "U$1") (pin "7") (pinfunction "V1P8_7") (pintype "bidirectional"))
    )
    (net (code "76") (name "Net-(U$1-V3P3)") (class "Default")
      (node (ref "C5") (pin "2") (pinfunction "2_2") (pintype "passive"))
      (node (ref "R1") (pin "1") (pinfunction "1_1") (pintype "passive"))
      (node (ref "R2") (pin "1") (pinfunction "1_1") (pintype "passive"))
      (node (ref "U$1") (pin "9") (pinfunction "V3P3_9") (pintype "bidirectional"))
    )
    (net (code "77") (name "Net-(U$1-VCP)") (class "Default")
      (node (ref "C1") (pin "2") (pinfunction "2_2") (pintype "passive"))
      (node (ref "U$1") (pin "1") (pinfunction "VCP_1") (pintype "bidirectional"))
    )
    (net (code "78") (name "Net-(U$1-VREG)") (class "Default")
      (node (ref "C3") (pin "2") (pinfunction "2_2") (pintype "passive"))
      (node (ref "L1") (pin "1") (pinfunction "1_1") (pintype "passive"))
      (node (ref "U$1") (pin "6") (pinfunction "VREG_6") (pintype "bidirectional"))
    )
    (net (code "79") (name "Net-(U$6-CPN)") (class "Default")
      (node (ref "C20") (pin "2") (pinfunction "2_2") (pintype "passive"))
      (node (ref "U$6") (pin "3") (pinfunction "CPN_3") (pintype "bidirectional"))
    )
    (net (code "80") (name "Net-(U$6-CPP)") (class "Default")
      (node (ref "C20") (pin "1") (pinfunction "1_1") (pintype "passive"))
      (node (ref "U$6") (pin "2") (pinfunction "CPP_2") (pintype "bidirectional"))
    )
    (net (code "81") (name "Net-(U$6-SW)") (class "Default")
      (node (ref "L3") (pin "2") (pinfunction "2_2") (pintype "passive"))
      (node (ref "U$6") (pin "4") (pinfunction "SW_4") (pintype "bidirectional"))
    )
    (net (code "82") (name "Net-(U$6-V1P8)") (class "Default")
      (node (ref "C22") (pin "2") (pinfunction "2_2") (pintype "passive"))
      (node (ref "U$6") (pin "7") (pinfunction "V1P8_7") (pintype "bidirectional"))
    )
    (net (code "83") (name "Net-(U$6-V3P3)") (class "Default")
      (node (ref "C23") (pin "2") (pinfunction "2_2") (pintype "passive"))
      (node (ref "R10") (pin "1") (pinfunction "1_1") (pintype "passive"))
      (node (ref "R11") (pin "1") (pinfunction "1_1") (pintype "passive"))
      (node (ref "U$6") (pin "9") (pinfunction "V3P3_9") (pintype "bidirectional"))
    )
    (net (code "84") (name "Net-(U$6-VCP)") (class "Default")
      (node (ref "C19") (pin "2") (pinfunction "2_2") (pintype "passive"))
      (node (ref "U$6") (pin "1") (pinfunction "VCP_1") (pintype "bidirectional"))
    )
    (net (code "85") (name "Net-(U$6-VREG)") (class "Default")
      (node (ref "C21") (pin "2") (pinfunction "2_2") (pintype "passive"))
      (node (ref "L3") (pin "1") (pinfunction "1_1") (pintype "passive"))
      (node (ref "U$6") (pin "6") (pinfunction "VREG_6") (pintype "bidirectional"))
    )
    (net (code "86") (name "Net-(U$7-CPN)") (class "Default")
      (node (ref "C26") (pin "2") (pinfunction "2_2") (pintype "passive"))
      (node (ref "U$7") (pin "3") (pinfunction "CPN_3") (pintype "bidirectional"))
    )
    (net (code "87") (name "Net-(U$7-CPP)") (class "Default")
      (node (ref "C26") (pin "1") (pinfunction "1_1") (pintype "passive"))
      (node (ref "U$7") (pin "2") (pinfunction "CPP_2") (pintype "bidirectional"))
    )
    (net (code "88") (name "Net-(U$7-SW)") (class "Default")
      (node (ref "L4") (pin "2") (pinfunction "2_2") (pintype "passive"))
      (node (ref "U$7") (pin "4") (pinfunction "SW_4") (pintype "bidirectional"))
    )
    (net (code "89") (name "Net-(U$7-V1P8)") (class "Default")
      (node (ref "C28") (pin "2") (pinfunction "2_2") (pintype "passive"))
      (node (ref "U$7") (pin "7") (pinfunction "V1P8_7") (pintype "bidirectional"))
    )
    (net (code "90") (name "Net-(U$7-V3P3)") (class "Default")
      (node (ref "C29") (pin "2") (pinfunction "2_2") (pintype "passive"))
      (node (ref "R12") (pin "1") (pinfunction "1_1") (pintype "passive"))
      (node (ref "R13") (pin "1") (pinfunction "1_1") (pintype "passive"))
      (node (ref "U$7") (pin "9") (pinfunction "V3P3_9") (pintype "bidirectional"))
    )
    (net (code "91") (name "Net-(U$7-VCP)") (class "Default")
      (node (ref "C25") (pin "2") (pinfunction "2_2") (pintype "passive"))
      (node (ref "U$7") (pin "1") (pinfunction "VCP_1") (pintype "bidirectional"))
    )
    (net (code "92") (name "Net-(U$7-VREG)") (class "Default")
      (node (ref "C27") (pin "2") (pinfunction "2_2") (pintype "passive"))
      (node (ref "L4") (pin "1") (pinfunction "1_1") (pintype "passive"))
      (node (ref "U$7") (pin "6") (pinfunction "VREG_6") (pintype "bidirectional"))
    )
    (net (code "93") (name "Net-(U1-VIN)") (class "Default")
      (node (ref "C10") (pin "1") (pinfunction "1_1") (pintype "passive"))
      (node (ref "J3") (pin "2") (pinfunction "2_2") (pintype "passive"))
      (node (ref "U1") (pin "2") (pinfunction "VIN_2") (pintype "power_in"))
    )
    (net (code "94") (name "Net-(U2-PA00(XIN32{slash}SER1:0{slash}TC2:0))") (class "Default")
      (node (ref "C8") (pin "2") (pinfunction "2_2") (pintype "passive"))
      (node (ref "U2") (pin "1") (pinfunction "PA00(XIN32/SER1:0/TC2:0)_1") (pintype "bidirectional"))
      (node (ref "Y1") (pin "P$1") (pinfunction "1_P$1") (pintype "passive"))
    )
    (net (code "95") (name "Net-(U2-PA01(XOUT32{slash}SER1:1{slash}TC2:1))") (class "Default")
      (node (ref "C7") (pin "2") (pinfunction "2_2") (pintype "passive"))
      (node (ref "U2") (pin "2") (pinfunction "PA01(XOUT32/SER1:1/TC2:1)_2") (pintype "bidirectional"))
      (node (ref "Y1") (pin "P$2") (pinfunction "2_P$2") (pintype "passive"))
    )
    (net (code "96") (name "Net-(U2-PA15(XOUT{slash}SER2:3+))") (class "Default")
      (node (ref "R19") (pin "1") (pinfunction "1_1") (pintype "passive"))
      (node (ref "U2") (pin "24") (pinfunction "PA15(XOUT/SER2:3+)_24") (pintype "bidirectional"))
    )
    (net (code "97") (name "Net-(U3-OUT1)") (class "Default")
      (node (ref "U$2") (pin "IN+") (pinfunction "IN+_IN+") (pintype "bidirectional"))
      (node (ref "U3") (pin "6") (pinfunction "OUT1_6") (pintype "output"))
      (node (ref "U3") (pin "7") (pinfunction "OUT2_7") (pintype "output"))
      (node (ref "U3") (pin "8") (pinfunction "OUT3_8") (pintype "output"))
    )
    (net (code "98") (name "Net-(U4-PD5(T1))") (class "Default")
      (node (ref "R20") (pin "1") (pinfunction "1_1") (pintype "passive"))
      (node (ref "U4") (pin "9") (pinfunction "PD5(T1)_9") (pintype "bidirectional"))
    )
    (net (code "99") (name "unconnected-(J1-Pad3)") (class "Default")
      (node (ref "J1") (pin "3") (pinfunction "3_3") (pintype "bidirectional"))
    )
    (net (code "100") (name "unconnected-(J1-Pad4)") (class "Default")
      (node (ref "J1") (pin "4") (pinfunction "4_4") (pintype "bidirectional"))
    )
    (net (code "101") (name "unconnected-(J1-Pad7)") (class "Default")
      (node (ref "J1") (pin "7") (pinfunction "7_7") (pintype "bidirectional"))
    )
    (net (code "102") (name "unconnected-(J1-Pad8)") (class "Default")
      (node (ref "J1") (pin "8") (pinfunction "8_8") (pintype "bidirectional"))
    )
    (net (code "103") (name "unconnected-(J1-Pad9)") (class "Default")
      (node (ref "J1") (pin "9") (pinfunction "9_9") (pintype "bidirectional"))
    )
    (net (code "104") (name "unconnected-(J1-Pad10)") (class "Default")
      (node (ref "J1") (pin "10") (pinfunction "10_10") (pintype "bidirectional"))
    )
    (net (code "105") (name "unconnected-(J1-Pad11)") (class "Default")
      (node (ref "J1") (pin "11") (pinfunction "11_11") (pintype "bidirectional"))
    )
    (net (code "106") (name "unconnected-(J1-Pad12)") (class "Default")
      (node (ref "J1") (pin "12") (pinfunction "12_12") (pintype "bidirectional"))
    )
    (net (code "107") (name "unconnected-(J1-Pad13)") (class "Default")
      (node (ref "J1") (pin "13") (pinfunction "13_13") (pintype "bidirectional"))
    )
    (net (code "108") (name "unconnected-(J1-Pad14)") (class "Default")
      (node (ref "J1") (pin "14") (pinfunction "14_14") (pintype "bidirectional"))
    )
    (net (code "109") (name "unconnected-(J1-Pad15)") (class "Default")
      (node (ref "J1") (pin "15") (pinfunction "15_15") (pintype "bidirectional"))
    )
    (net (code "110") (name "unconnected-(J1-Pad16)") (class "Default")
      (node (ref "J1") (pin "16") (pinfunction "16_16") (pintype "bidirectional"))
    )
    (net (code "111") (name "unconnected-(J1-Pad17)") (class "Default")
      (node (ref "J1") (pin "17") (pinfunction "17_17") (pintype "bidirectional"))
    )
    (net (code "112") (name "unconnected-(J1-Pad18)") (class "Default")
      (node (ref "J1") (pin "18") (pinfunction "18_18") (pintype "bidirectional"))
    )
    (net (code "113") (name "unconnected-(J1-Pad19)") (class "Default")
      (node (ref "J1") (pin "19") (pinfunction "19_19") (pintype "bidirectional"))
    )
    (net (code "114") (name "unconnected-(J1-Pad20)") (class "Default")
      (node (ref "J1") (pin "20") (pinfunction "20_20") (pintype "bidirectional"))
    )
    (net (code "115") (name "unconnected-(J1-Pad21)") (class "Default")
      (node (ref "J1") (pin "21") (pinfunction "21_21") (pintype "bidirectional"))
    )
    (net (code "116") (name "unconnected-(J1-Pad22)") (class "Default")
      (node (ref "J1") (pin "22") (pinfunction "22_22") (pintype "bidirectional"))
    )
    (net (code "117") (name "unconnected-(J1-Pad23)") (class "Default")
      (node (ref "J1") (pin "23") (pinfunction "23_23") (pintype "bidirectional"))
    )
    (net (code "118") (name "unconnected-(J1-Pad24)") (class "Default")
      (node (ref "J1") (pin "24") (pinfunction "24_24") (pintype "bidirectional"))
    )
    (net (code "119") (name "unconnected-(J1-Pad25)") (class "Default")
      (node (ref "J1") (pin "25") (pinfunction "25_25") (pintype "bidirectional"))
    )
    (net (code "120") (name "unconnected-(J1-Pad26)") (class "Default")
      (node (ref "J1") (pin "26") (pinfunction "26_26") (pintype "bidirectional"))
    )
    (net (code "121") (name "unconnected-(J1-Pad27)") (class "Default")
      (node (ref "J1") (pin "27") (pinfunction "27_27") (pintype "bidirectional"))
    )
    (net (code "122") (name "unconnected-(J1-Pad28)") (class "Default")
      (node (ref "J1") (pin "28") (pinfunction "28_28") (pintype "bidirectional"))
    )
    (net (code "123") (name "unconnected-(J1-Pad29)") (class "Default")
      (node (ref "J1") (pin "29") (pinfunction "29_29") (pintype "bidirectional"))
    )
    (net (code "124") (name "unconnected-(J1-Pad30)") (class "Default")
      (node (ref "J1") (pin "30") (pinfunction "30_30") (pintype "bidirectional"))
    )
    (net (code "125") (name "unconnected-(J1-Pad31)") (class "Default")
      (node (ref "J1") (pin "31") (pinfunction "31_31") (pintype "bidirectional"))
    )
    (net (code "126") (name "unconnected-(J1-Pad32)") (class "Default")
      (node (ref "J1") (pin "32") (pinfunction "32_32") (pintype "bidirectional"))
    )
    (net (code "127") (name "unconnected-(J1-Pad33)") (class "Default")
      (node (ref "J1") (pin "33") (pinfunction "33_33") (pintype "bidirectional"))
    )
    (net (code "128") (name "unconnected-(J1-Pad34)") (class "Default")
      (node (ref "J1") (pin "34") (pinfunction "34_34") (pintype "bidirectional"))
    )
    (net (code "129") (name "unconnected-(J1-Pad35)") (class "Default")
      (node (ref "J1") (pin "35") (pinfunction "35_35") (pintype "bidirectional"))
    )
    (net (code "130") (name "unconnected-(J1-Pad36)") (class "Default")
      (node (ref "J1") (pin "36") (pinfunction "36_36") (pintype "bidirectional"))
    )
    (net (code "131") (name "unconnected-(J1-Pad37)") (class "Default")
      (node (ref "J1") (pin "37") (pinfunction "37_37") (pintype "bidirectional"))
    )
    (net (code "132") (name "unconnected-(J1-Pad38)") (class "Default")
      (node (ref "J1") (pin "38") (pinfunction "38_38") (pintype "bidirectional"))
    )
    (net (code "133") (name "unconnected-(J1-Pad39)") (class "Default")
      (node (ref "J1") (pin "39") (pinfunction "39_39") (pintype "bidirectional"))
    )
    (net (code "134") (name "unconnected-(J1-Pad40)") (class "Default")
      (node (ref "J1") (pin "40") (pinfunction "40_40") (pintype "bidirectional"))
    )
    (net (code "135") (name "unconnected-(J1-Pad41)") (class "Default")
      (node (ref "J1") (pin "41") (pinfunction "41_41") (pintype "bidirectional"))
    )
    (net (code "136") (name "unconnected-(J1-Pad42)") (class "Default")
      (node (ref "J1") (pin "42") (pinfunction "42_42") (pintype "bidirectional"))
    )
    (net (code "137") (name "unconnected-(J1-Pad43)") (class "Default")
      (node (ref "J1") (pin "43") (pinfunction "43_43") (pintype "bidirectional"))
    )
    (net (code "138") (name "unconnected-(J1-Pad44)") (class "Default")
      (node (ref "J1") (pin "44") (pinfunction "44_44") (pintype "bidirectional"))
    )
    (net (code "139") (name "unconnected-(J1-Pad45)") (class "Default")
      (node (ref "J1") (pin "45") (pinfunction "45_45") (pintype "bidirectional"))
    )
    (net (code "140") (name "unconnected-(J1-Pad46)") (class "Default")
      (node (ref "J1") (pin "46") (pinfunction "46_46") (pintype "bidirectional"))
    )
    (net (code "141") (name "unconnected-(J1-Pad47)") (class "Default")
      (node (ref "J1") (pin "47") (pinfunction "47_47") (pintype "bidirectional"))
    )
    (net (code "142") (name "unconnected-(J1-Pad48)") (class "Default")
      (node (ref "J1") (pin "48") (pinfunction "48_48") (pintype "bidirectional"))
    )
    (net (code "143") (name "unconnected-(J1-Pad49)") (class "Default")
      (node (ref "J1") (pin "49") (pinfunction "49_49") (pintype "bidirectional"))
    )
    (net (code "144") (name "unconnected-(J1-Pad50)") (class "Default")
      (node (ref "J1") (pin "50") (pinfunction "50_50") (pintype "bidirectional"))
    )
    (net (code "145") (name "unconnected-(J1-Pad51)") (class "Default")
      (node (ref "J1") (pin "51") (pinfunction "51_51") (pintype "bidirectional"))
    )
    (net (code "146") (name "unconnected-(J1-Pad53)") (class "Default")
      (node (ref "J1") (pin "53") (pinfunction "53_53") (pintype "bidirectional"))
    )
    (net (code "147") (name "unconnected-(J1-Pad54)") (class "Default")
      (node (ref "J1") (pin "54") (pinfunction "54_54") (pintype "bidirectional"))
    )
    (net (code "148") (name "unconnected-(J1-Pad55)") (class "Default")
      (node (ref "J1") (pin "55") (pinfunction "55_55") (pintype "bidirectional"))
    )
    (net (code "149") (name "unconnected-(J1-Pad56)") (class "Default")
      (node (ref "J1") (pin "56") (pinfunction "56_56") (pintype "bidirectional"))
    )
    (net (code "150") (name "unconnected-(J1-Pad57)") (class "Default")
      (node (ref "J1") (pin "57") (pinfunction "57_57") (pintype "bidirectional"))
    )
    (net (code "151") (name "unconnected-(J1-Pad58)") (class "Default")
      (node (ref "J1") (pin "58") (pinfunction "58_58") (pintype "bidirectional"))
    )
    (net (code "152") (name "unconnected-(J1-Pad59)") (class "Default")
      (node (ref "J1") (pin "59") (pinfunction "59_59") (pintype "bidirectional"))
    )
    (net (code "153") (name "unconnected-(J1-Pad60)") (class "Default")
      (node (ref "J1") (pin "60") (pinfunction "60_60") (pintype "bidirectional"))
    )
    (net (code "154") (name "unconnected-(J1-Pad61)") (class "Default")
      (node (ref "J1") (pin "61") (pinfunction "61_61") (pintype "bidirectional"))
    )
    (net (code "155") (name "unconnected-(J1-Pad62)") (class "Default")
      (node (ref "J1") (pin "62") (pinfunction "62_62") (pintype "bidirectional"))
    )
    (net (code "156") (name "unconnected-(J1-Pad63)") (class "Default")
      (node (ref "J1") (pin "63") (pinfunction "63_63") (pintype "bidirectional"))
    )
    (net (code "157") (name "unconnected-(J1-Pad64)") (class "Default")
      (node (ref "J1") (pin "64") (pinfunction "64_64") (pintype "bidirectional"))
    )
    (net (code "158") (name "unconnected-(J1-Pad66)") (class "Default")
      (node (ref "J1") (pin "66") (pinfunction "66_66") (pintype "bidirectional"))
    )
    (net (code "159") (name "unconnected-(J1-Pad68)") (class "Default")
      (node (ref "J1") (pin "68") (pinfunction "68_68") (pintype "bidirectional"))
    )
    (net (code "160") (name "unconnected-(J1-Pad69)") (class "Default")
      (node (ref "J1") (pin "69") (pinfunction "69_69") (pintype "bidirectional"))
    )
    (net (code "161") (name "unconnected-(J1-Pad70)") (class "Default")
      (node (ref "J1") (pin "70") (pinfunction "70_70") (pintype "bidirectional"))
    )
    (net (code "162") (name "unconnected-(J1-Pad71)") (class "Default")
      (node (ref "J1") (pin "71") (pinfunction "71_71") (pintype "bidirectional"))
    )
    (net (code "163") (name "unconnected-(J1-Pad72)") (class "Default")
      (node (ref "J1") (pin "72") (pinfunction "72_72") (pintype "bidirectional"))
    )
    (net (code "164") (name "unconnected-(J1-Pad73)") (class "Default")
      (node (ref "J1") (pin "73") (pinfunction "73_73") (pintype "bidirectional"))
    )
    (net (code "165") (name "unconnected-(J1-Pad74)") (class "Default")
      (node (ref "J1") (pin "74") (pinfunction "74_74") (pintype "bidirectional"))
    )
    (net (code "166") (name "unconnected-(J1-Pad76)") (class "Default")
      (node (ref "J1") (pin "76") (pinfunction "76_76") (pintype "bidirectional"))
    )
    (net (code "167") (name "unconnected-(J1-Pad77)") (class "Default")
      (node (ref "J1") (pin "77") (pinfunction "77_77") (pintype "bidirectional"))
    )
    (net (code "168") (name "unconnected-(J1-Pad78)") (class "Default")
      (node (ref "J1") (pin "78") (pinfunction "78_78") (pintype "bidirectional"))
    )
    (net (code "169") (name "unconnected-(J1-Pad79)") (class "Default")
      (node (ref "J1") (pin "79") (pinfunction "79_79") (pintype "bidirectional"))
    )
    (net (code "170") (name "unconnected-(J1-Pad80)") (class "Default")
      (node (ref "J1") (pin "80") (pinfunction "80_80") (pintype "bidirectional"))
    )
    (net (code "171") (name "unconnected-(J1-Pad81)") (class "Default")
      (node (ref "J1") (pin "81") (pinfunction "81_81") (pintype "bidirectional"))
    )
    (net (code "172") (name "unconnected-(J1-Pad82)") (class "Default")
      (node (ref "J1") (pin "82") (pinfunction "82_82") (pintype "bidirectional"))
    )
    (net (code "173") (name "unconnected-(J1-Pad83)") (class "Default")
      (node (ref "J1") (pin "83") (pinfunction "83_83") (pintype "bidirectional"))
    )
    (net (code "174") (name "unconnected-(J1-Pad84)") (class "Default")
      (node (ref "J1") (pin "84") (pinfunction "84_84") (pintype "bidirectional"))
    )
    (net (code "175") (name "unconnected-(J1-Pad85)") (class "Default")
      (node (ref "J1") (pin "85") (pinfunction "85_85") (pintype "bidirectional"))
    )
    (net (code "176") (name "unconnected-(J1-Pad86)") (class "Default")
      (node (ref "J1") (pin "86") (pinfunction "86_86") (pintype "bidirectional"))
    )
    (net (code "177") (name "unconnected-(J1-Pad87)") (class "Default")
      (node (ref "J1") (pin "87") (pinfunction "87_87") (pintype "bidirectional"))
    )
    (net (code "178") (name "unconnected-(J1-Pad88)") (class "Default")
      (node (ref "J1") (pin "88") (pinfunction "88_88") (pintype "bidirectional"))
    )
    (net (code "179") (name "unconnected-(J1-Pad89)") (class "Default")
      (node (ref "J1") (pin "89") (pinfunction "89_89") (pintype "bidirectional"))
    )
    (net (code "180") (name "unconnected-(J1-Pad90)") (class "Default")
      (node (ref "J1") (pin "90") (pinfunction "90_90") (pintype "bidirectional"))
    )
    (net (code "181") (name "unconnected-(J1-Pad92)") (class "Default")
      (node (ref "J1") (pin "92") (pinfunction "92_92") (pintype "bidirectional"))
    )
    (net (code "182") (name "unconnected-(J1-Pad95)") (class "Default")
      (node (ref "J1") (pin "95") (pinfunction "95_95") (pintype "bidirectional"))
    )
    (net (code "183") (name "unconnected-(J1-Pad96)") (class "Default")
      (node (ref "J1") (pin "96") (pinfunction "96_96") (pintype "bidirectional"))
    )
    (net (code "184") (name "unconnected-(J1-Pad97)") (class "Default")
      (node (ref "J1") (pin "97") (pinfunction "97_97") (pintype "bidirectional"))
    )
    (net (code "185") (name "unconnected-(J1-Pad98)") (class "Default")
      (node (ref "J1") (pin "98") (pinfunction "98_98") (pintype "bidirectional"))
    )
    (net (code "186") (name "unconnected-(J1-Pad99)") (class "Default")
      (node (ref "J1") (pin "99") (pinfunction "99_99") (pintype "bidirectional"))
    )
    (net (code "187") (name "unconnected-(J1-Pad100)") (class "Default")
      (node (ref "J1") (pin "100") (pinfunction "100_100") (pintype "bidirectional"))
    )
    (net (code "188") (name "unconnected-(J1-Pad102)") (class "Default")
      (node (ref "J1") (pin "102") (pinfunction "102_102") (pintype "bidirectional"))
    )
    (net (code "189") (name "unconnected-(J1-Pad103)") (class "Default")
      (node (ref "J1") (pin "103") (pinfunction "103_103") (pintype "bidirectional"))
    )
    (net (code "190") (name "unconnected-(J1-Pad104)") (class "Default")
      (node (ref "J1") (pin "104") (pinfunction "104_104") (pintype "bidirectional"))
    )
    (net (code "191") (name "unconnected-(S1-O-Pad1)") (class "Default")
      (node (ref "S1") (pin "1") (pinfunction "O_1") (pintype "passive"))
    )
    (net (code "192") (name "unconnected-(S2-O-Pad1)") (class "Default")
      (node (ref "S2") (pin "1") (pinfunction "O_1") (pintype "passive"))
    )
    (net (code "193") (name "unconnected-(U2-PA03(AIN1{slash}REFA)-Pad4)") (class "Default")
      (node (ref "U2") (pin "4") (pinfunction "PA03(AIN1/REFA)_4") (pintype "bidirectional"))
    )
    (net (code "194") (name "unconnected-(U2-PA04(AIN4{slash}REFB{slash}SER0:0{slash}TC0:0)-Pad9)") (class "Default")
      (node (ref "U2") (pin "9") (pinfunction "PA04(AIN4/REFB/SER0:0/TC0:0)_9") (pintype "bidirectional"))
    )
    (net (code "195") (name "unconnected-(U2-PA05(AIN5{slash}SER0:1{slash}TC0:1)-Pad10)") (class "Default")
      (node (ref "U2") (pin "10") (pinfunction "PA05(AIN5/SER0:1/TC0:1)_10") (pintype "bidirectional"))
    )
    (net (code "196") (name "unconnected-(U2-PA06(AIN6{slash}SER0:2{slash}TC1:0)-Pad11)") (class "Default")
      (node (ref "U2") (pin "11") (pinfunction "PA06(AIN6/SER0:2/TC1:0)_11") (pintype "bidirectional"))
    )
    (net (code "197") (name "unconnected-(U2-PA07(AIN7{slash}SER0:3{slash}TC1:1)-Pad12)") (class "Default")
      (node (ref "U2") (pin "12") (pinfunction "PA07(AIN7/SER0:3/TC1:1)_12") (pintype "bidirectional"))
    )
    (net (code "198") (name "unconnected-(U2-PA10(AIN18{slash}SER0:2+)-Pad15)") (class "Default")
      (node (ref "U2") (pin "15") (pinfunction "PA10(AIN18/SER0:2+)_15") (pintype "bidirectional"))
    )
    (net (code "199") (name "unconnected-(U2-PA11(AIN19{slash}SER0:3+)-Pad16)") (class "Default")
      (node (ref "U2") (pin "16") (pinfunction "PA11(AIN19/SER0:3+)_16") (pintype "bidirectional"))
    )
    (net (code "200") (name "unconnected-(U2-PA12(I2C{slash}SER2:0+)-Pad21)") (class "Default")
      (node (ref "U2") (pin "21") (pinfunction "PA12(I2C/SER2:0+)_21") (pintype "bidirectional"))
    )
    (net (code "201") (name "unconnected-(U2-PA13(I2C{slash}SER2:1+)-Pad22)") (class "Default")
      (node (ref "U2") (pin "22") (pinfunction "PA13(I2C/SER2:1+)_22") (pintype "bidirectional"))
    )
    (net (code "202") (name "unconnected-(U2-PA14(XIN{slash}SER2:2+)-Pad23)") (class "Default")
      (node (ref "U2") (pin "23") (pinfunction "PA14(XIN/SER2:2+)_23") (pintype "bidirectional"))
    )
    (net (code "203") (name "unconnected-(U2-PA18(SER1:2+)-Pad27)") (class "Default")
      (node (ref "U2") (pin "27") (pinfunction "PA18(SER1:2+)_27") (pintype "bidirectional"))
    )
    (net (code "204") (name "unconnected-(U2-PA19(SER1:3+)-Pad28)") (class "Default")
      (node (ref "U2") (pin "28") (pinfunction "PA19(SER1:3+)_28") (pintype "bidirectional"))
    )
    (net (code "205") (name "unconnected-(U2-PA20(SER5:2+)-Pad29)") (class "Default")
      (node (ref "U2") (pin "29") (pinfunction "PA20(SER5:2+)_29") (pintype "bidirectional"))
    )
    (net (code "206") (name "unconnected-(U2-PA21(SER5:3+)-Pad30)") (class "Default")
      (node (ref "U2") (pin "30") (pinfunction "PA21(SER5:3+)_30") (pintype "bidirectional"))
    )
    (net (code "207") (name "unconnected-(U2-PA27-Pad39)") (class "Default")
      (node (ref "U2") (pin "39") (pinfunction "PA27_39") (pintype "bidirectional"))
    )
    (net (code "208") (name "unconnected-(U2-PB02(AIN10{slash}SER5:0)-Pad47)") (class "Default")
      (node (ref "U2") (pin "47") (pinfunction "PB02(AIN10/SER5:0)_47") (pintype "bidirectional"))
    )
    (net (code "209") (name "unconnected-(U2-PB03(AIN11{slash}SER5:1)-Pad48)") (class "Default")
      (node (ref "U2") (pin "48") (pinfunction "PB03(AIN11/SER5:1)_48") (pintype "bidirectional"))
    )
    (net (code "210") (name "unconnected-(U2-PB08(AIN2{slash}SER4:0{slash}TC4:0)-Pad7)") (class "Default")
      (node (ref "U2") (pin "7") (pinfunction "PB08(AIN2/SER4:0/TC4:0)_7") (pintype "bidirectional"))
    )
    (net (code "211") (name "unconnected-(U2-PB09(AIN3{slash}SER4:1{slash}TC4:1)-Pad8)") (class "Default")
      (node (ref "U2") (pin "8") (pinfunction "PB09(AIN3/SER4:1/TC4:1)_8") (pintype "bidirectional"))
    )
    (net (code "212") (name "unconnected-(U2-PB10(SER4:2+)-Pad19)") (class "Default")
      (node (ref "U2") (pin "19") (pinfunction "PB10(SER4:2+)_19") (pintype "bidirectional"))
    )
    (net (code "213") (name "unconnected-(U2-PB11(SER4:3+)-Pad20)") (class "Default")
      (node (ref "U2") (pin "20") (pinfunction "PB11(SER4:3+)_20") (pintype "bidirectional"))
    )
    (net (code "214") (name "unconnected-(U2-PB22(SER5:2+)-Pad37)") (class "Default")
      (node (ref "U2") (pin "37") (pinfunction "PB22(SER5:2+)_37") (pintype "bidirectional"))
    )
    (net (code "215") (name "unconnected-(U2-PB23(SER5:3+)-Pad38)") (class "Default")
      (node (ref "U2") (pin "38") (pinfunction "PB23(SER5:3+)_38") (pintype "bidirectional"))
    )
    (net (code "216") (name "unconnected-(U2-VDDIO-Pad17)") (class "Default")
      (node (ref "U2") (pin "17") (pinfunction "VDDIO_17") (pintype "bidirectional"))
    )
    (net (code "217") (name "unconnected-(U2-VDDIO-Pad36)") (class "Default")
      (node (ref "U2") (pin "36") (pinfunction "VDDIO_36") (pintype "bidirectional"))
    )
    (net (code "218") (name "unconnected-(U3-NC-Pad5)") (class "Default")
      (node (ref "U3") (pin "5") (pinfunction "NC_5") (pintype "passive"))
    )
    (net (code "219") (name "unconnected-(U4-AGND-Pad21)") (class "Default")
      (node (ref "U4") (pin "21") (pinfunction "AGND_21") (pintype "bidirectional"))
    )
    (net (code "220") (name "unconnected-(U4-AREF-Pad20)") (class "Default")
      (node (ref "U4") (pin "20") (pinfunction "AREF_20") (pintype "bidirectional"))
    )
    (net (code "221") (name "unconnected-(U4-PB0(ICP)-Pad12)") (class "Default")
      (node (ref "U4") (pin "12") (pinfunction "PB0(ICP)_12") (pintype "bidirectional"))
    )
    (net (code "222") (name "unconnected-(U4-PB1(OC1A)-Pad13)") (class "Default")
      (node (ref "U4") (pin "13") (pinfunction "PB1(OC1A)_13") (pintype "bidirectional"))
    )
    (net (code "223") (name "unconnected-(U4-PB2(SS{slash}OC1B)-Pad14)") (class "Default")
      (node (ref "U4") (pin "14") (pinfunction "PB2(SS/OC1B)_14") (pintype "bidirectional"))
    )
    (net (code "224") (name "unconnected-(U4-PC2(ADC2)-Pad25)") (class "Default")
      (node (ref "U4") (pin "25") (pinfunction "PC2(ADC2)_25") (pintype "bidirectional"))
    )
    (net (code "225") (name "unconnected-(U4-PC3(ADC3)-Pad26)") (class "Default")
      (node (ref "U4") (pin "26") (pinfunction "PC3(ADC3)_26") (pintype "bidirectional"))
    )
    (net (code "226") (name "unconnected-(U4-PD4(XCK{slash}T0)-Pad2)") (class "Default")
      (node (ref "U4") (pin "2") (pinfunction "PD4(XCK/T0)_2") (pintype "bidirectional"))
    )
    (net (code "227") (name "unconnected-(U4-PD6(AIN0)-Pad10)") (class "Default")
      (node (ref "U4") (pin "10") (pinfunction "PD6(AIN0)_10") (pintype "bidirectional"))
    )
    (net (code "228") (name "unconnected-(U4-PD7(AIN1)-Pad11)") (class "Default")
      (node (ref "U4") (pin "11") (pinfunction "PD7(AIN1)_11") (pintype "bidirectional"))
    )
  )
)
